# 02-MeasurementChannels.net
KiCad netlist of a schematic drawn in Altium Designer
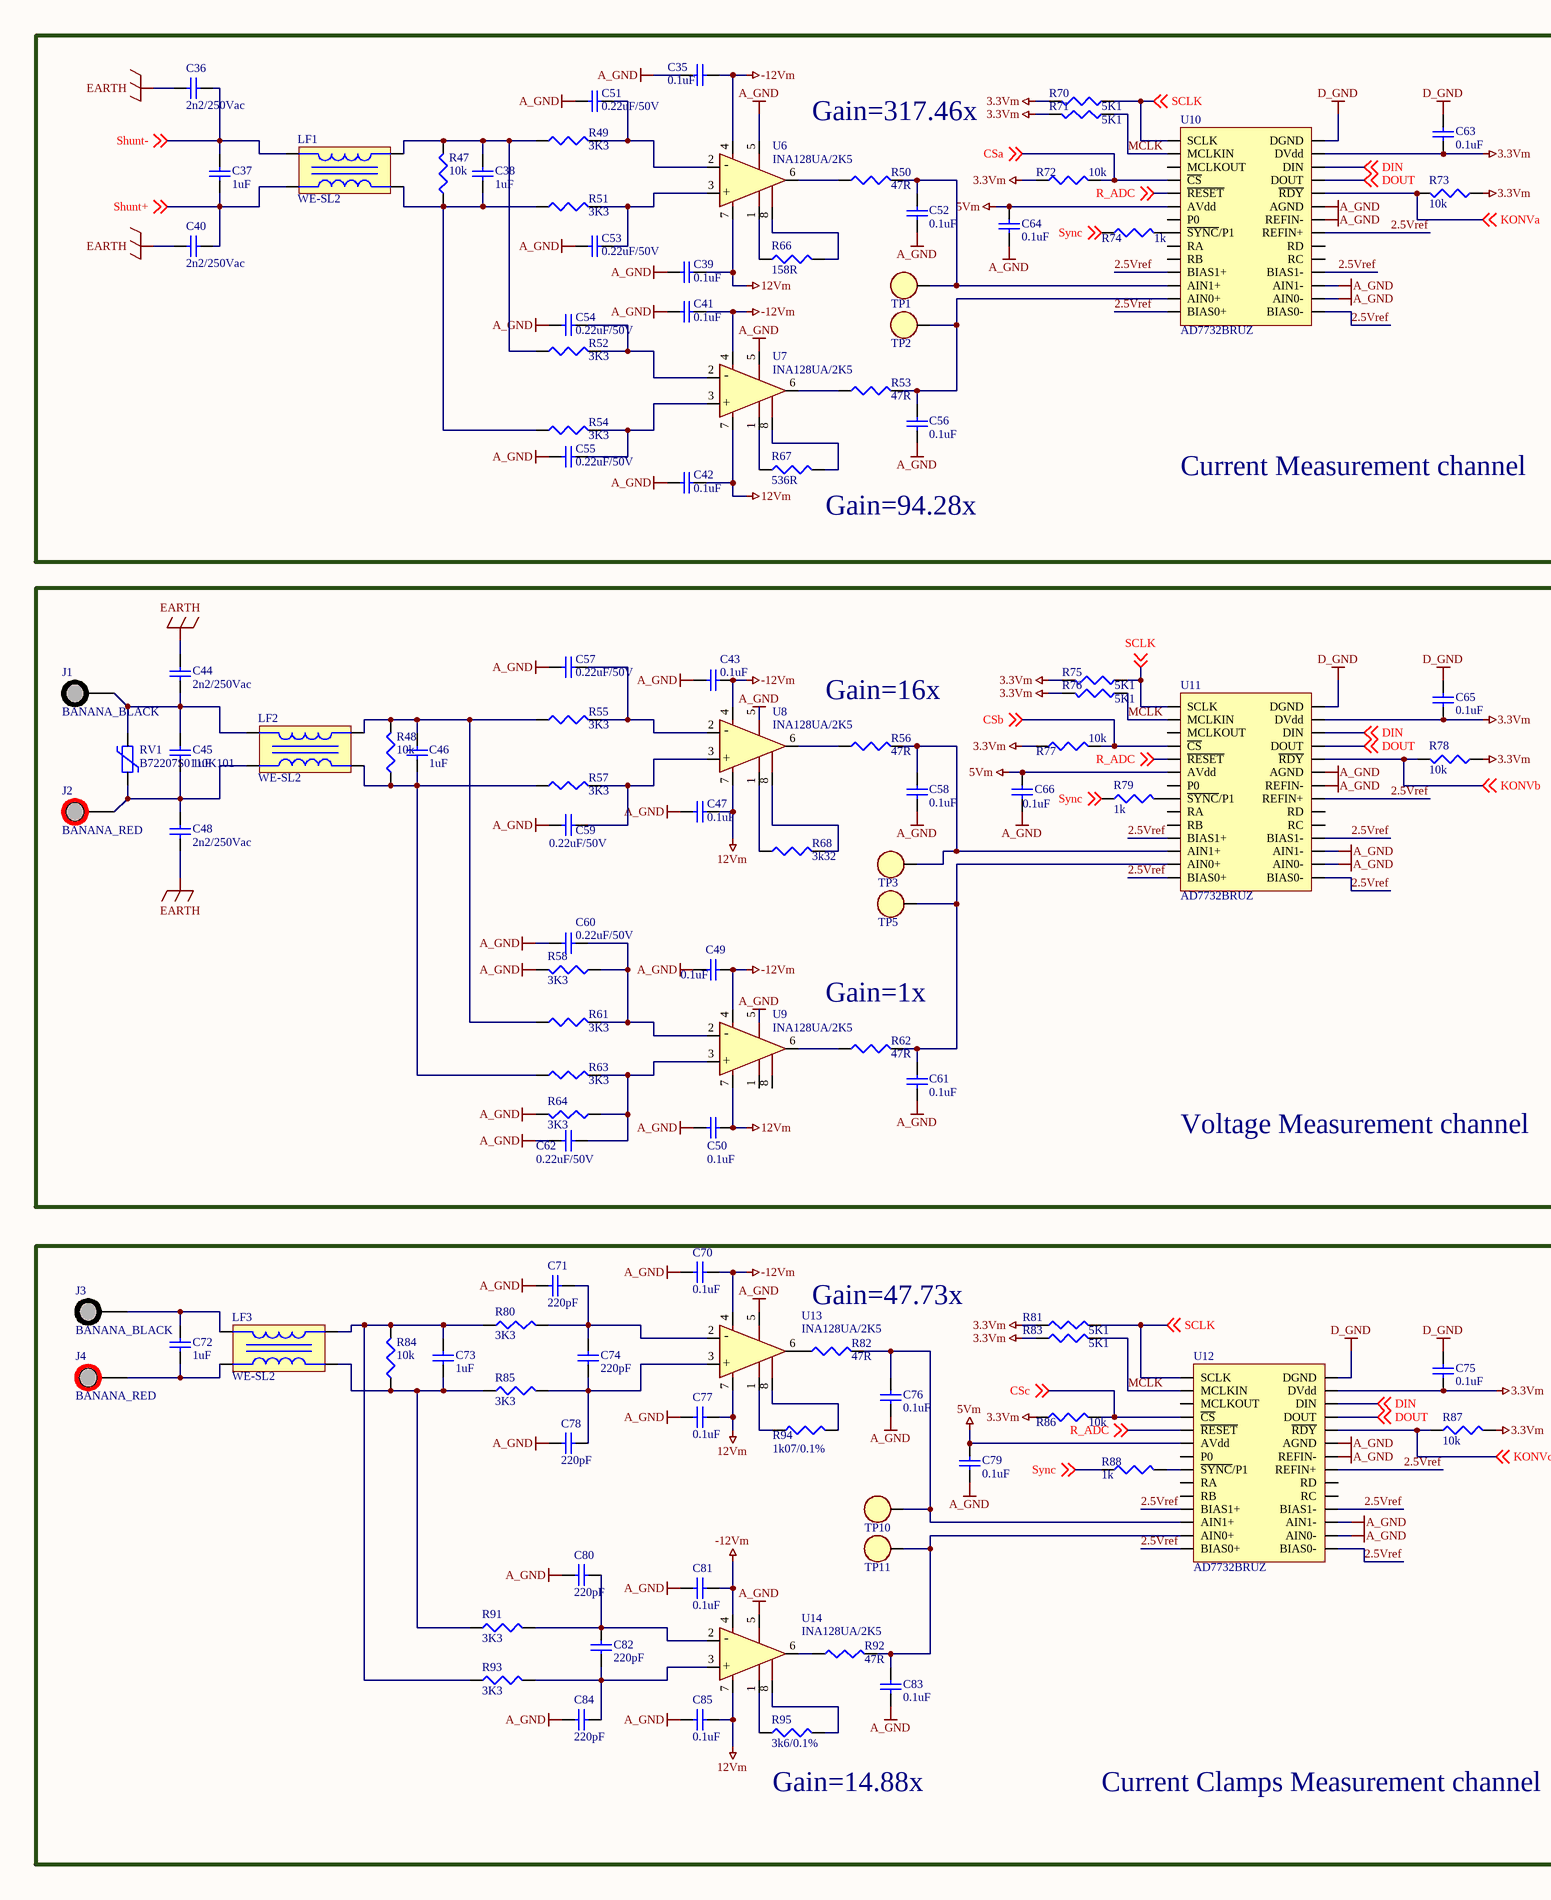
[diagram p0: 02-MeasurementChannels.SchDoc, left]
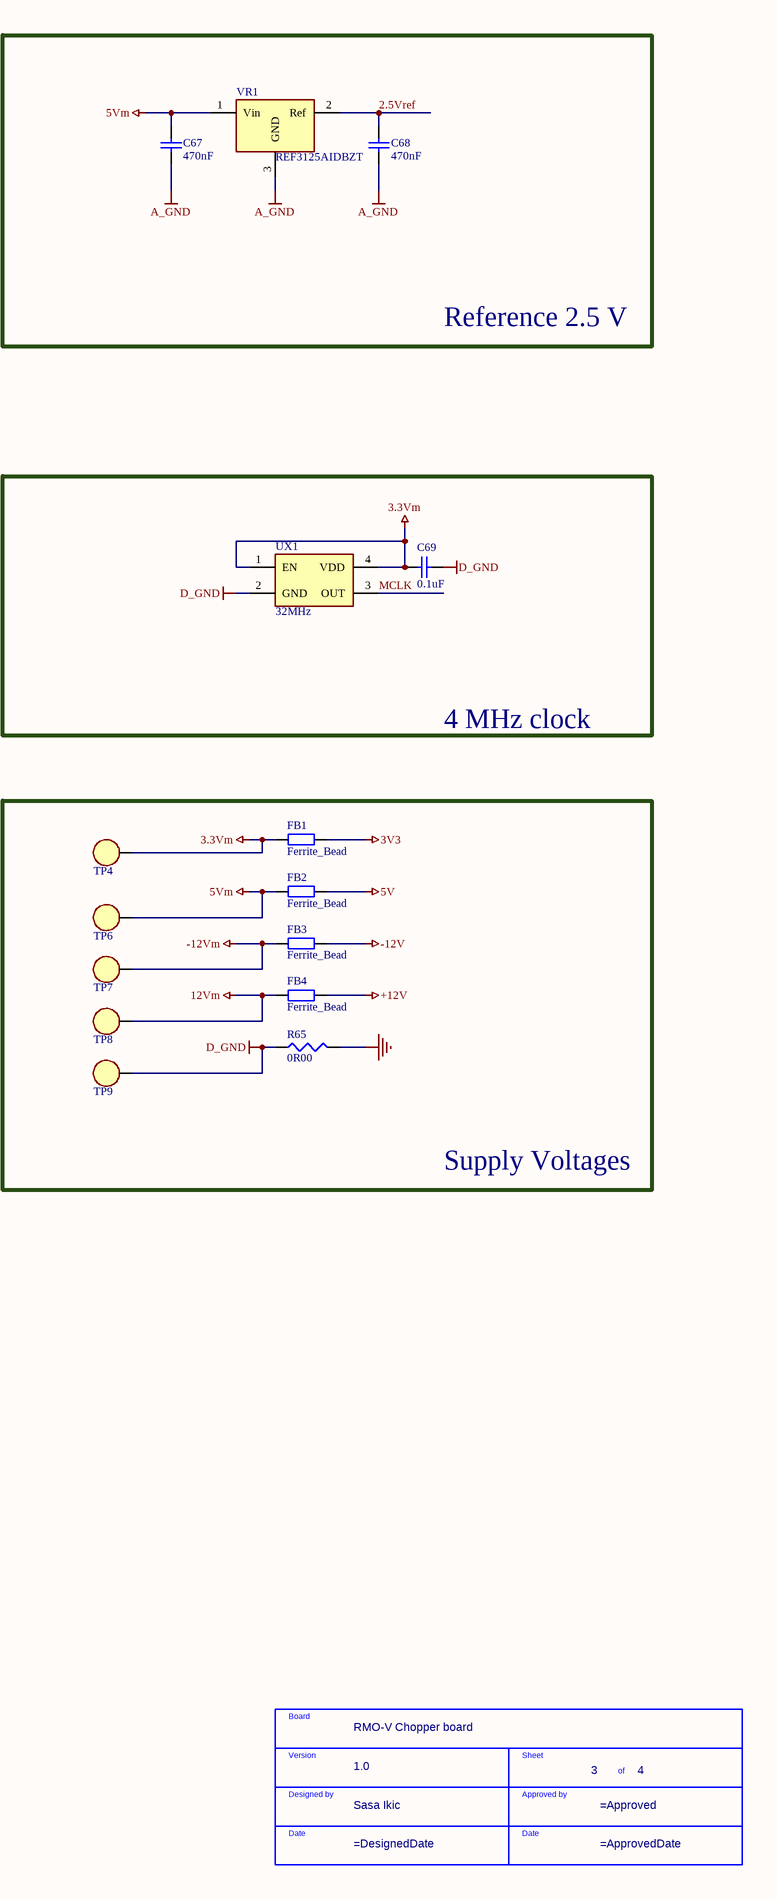
[diagram p1: 02-MeasurementChannels.SchDoc, right]

(export (version "E")
  (design (tool "Eeschema 10.0.6"))
  (components
    (comp (ref "C35")
      (value "0.1uF")
      (footprint "C0805")
      (description "CAP 0.1uF 0805 50V")
      (fields
        (field (name "MANUFACTURER") "KEMET")
        (field (name "MANUFACTURER PART NUMBER") "08055C104KAT2A")
        (field (name ".PCBCHECKED") "BP")
        (field (name ".SCHCHECKED") "BP")
      )
      (libsource (lib "My Library") (part "08055C104KAT2A"))
    )
    (comp (ref "C36")
      (value "2n2/250Vac")
      (footprint "CAPC3426X27N")
      (description "Cap Ceramic 0.0022uF 250VAC X7R 10% SMD 2220 Embossed T/R")
      (fields
        (field (name "MANUFACTURER") "Murata")
        (field (name "MANUFACTURER PART NUMBER") "GA355QR7GF222KW01L")
      )
      (libsource (lib "RMOV_chopper") (part "GA355QR7GF222KW01L"))
    )
    (comp (ref "C37")
      (value "1uF")
      (footprint "C0805")
      (description "CAP 1UF 0805 25V")
      (fields
        (field (name "MANUFACTURER") "KEMET")
        (field (name "MANUFACTURER PART NUMBER") "C0805C105K3RACTU")
        (field (name ".PCBCHECKED") "BP")
        (field (name ".SCHCHECKED") "BP")
      )
      (libsource (lib "My Library") (part "C0805C105K3RACTU"))
    )
    (comp (ref "C38")
      (value "1uF")
      (footprint "C0805")
      (description "CAP 1UF 0805 25V")
      (fields
        (field (name "MANUFACTURER") "KEMET")
        (field (name "MANUFACTURER PART NUMBER") "C0805C105K3RACTU")
        (field (name ".PCBCHECKED") "BP")
        (field (name ".SCHCHECKED") "BP")
      )
      (libsource (lib "My Library") (part "C0805C105K3RACTU"))
    )
    (comp (ref "C39")
      (value "0.1uF")
      (footprint "C0805")
      (description "CAP 0.1uF 0805 50V")
      (fields
        (field (name "MANUFACTURER") "KEMET")
        (field (name "MANUFACTURER PART NUMBER") "08055C104KAT2A")
        (field (name ".PCBCHECKED") "BP")
        (field (name ".SCHCHECKED") "BP")
      )
      (libsource (lib "My Library") (part "08055C104KAT2A"))
    )
    (comp (ref "C40")
      (value "2n2/250Vac")
      (footprint "CAPC3426X27N")
      (description "Cap Ceramic 0.0022uF 250VAC X7R 10% SMD 2220 Embossed T/R")
      (fields
        (field (name "MANUFACTURER") "Murata")
        (field (name "MANUFACTURER PART NUMBER") "GA355QR7GF222KW01L")
      )
      (libsource (lib "RMOV_chopper") (part "GA355QR7GF222KW01L"))
    )
    (comp (ref "C41")
      (value "0.1uF")
      (footprint "C0805")
      (description "CAP 0.1uF 0805 50V")
      (fields
        (field (name "MANUFACTURER") "KEMET")
        (field (name "MANUFACTURER PART NUMBER") "08055C104KAT2A")
        (field (name ".PCBCHECKED") "BP")
        (field (name ".SCHCHECKED") "BP")
      )
      (libsource (lib "My Library") (part "08055C104KAT2A"))
    )
    (comp (ref "C42")
      (value "0.1uF")
      (footprint "C0805")
      (description "CAP 0.1uF 0805 50V")
      (fields
        (field (name "MANUFACTURER") "KEMET")
        (field (name "MANUFACTURER PART NUMBER") "08055C104KAT2A")
        (field (name ".PCBCHECKED") "BP")
        (field (name ".SCHCHECKED") "BP")
      )
      (libsource (lib "My Library") (part "08055C104KAT2A"))
    )
    (comp (ref "C43")
      (value "0.1uF")
      (footprint "C0805")
      (description "CAP 0.1uF 0805 50V")
      (fields
        (field (name "MANUFACTURER") "KEMET")
        (field (name "MANUFACTURER PART NUMBER") "08055C104KAT2A")
        (field (name ".PCBCHECKED") "BP")
        (field (name ".SCHCHECKED") "BP")
      )
      (libsource (lib "My Library") (part "08055C104KAT2A"))
    )
    (comp (ref "C44")
      (value "2n2/250Vac")
      (footprint "CAPC3426X27N")
      (description "Cap Ceramic 0.0022uF 250VAC X7R 10% SMD 2220 Embossed T/R")
      (fields
        (field (name "MANUFACTURER") "Murata")
        (field (name "MANUFACTURER PART NUMBER") "GA355QR7GF222KW01L")
      )
      (libsource (lib "RMOV_chopper") (part "GA355QR7GF222KW01L"))
    )
    (comp (ref "C45")
      (value "1uF")
      (footprint "C0805")
      (description "CAP 1UF 0805 25V")
      (fields
        (field (name "MANUFACTURER") "KEMET")
        (field (name "MANUFACTURER PART NUMBER") "C0805C105K3RACTU")
        (field (name ".PCBCHECKED") "BP")
        (field (name ".SCHCHECKED") "BP")
      )
      (libsource (lib "My Library") (part "C0805C105K3RACTU"))
    )
    (comp (ref "C46")
      (value "1uF")
      (footprint "C0805")
      (description "CAP 1UF 0805 25V")
      (fields
        (field (name "MANUFACTURER") "KEMET")
        (field (name "MANUFACTURER PART NUMBER") "C0805C105K3RACTU")
        (field (name ".PCBCHECKED") "BP")
        (field (name ".SCHCHECKED") "BP")
      )
      (libsource (lib "My Library") (part "C0805C105K3RACTU"))
    )
    (comp (ref "C47")
      (value "0.1uF")
      (footprint "C0805")
      (description "CAP 0.1uF 0805 50V")
      (fields
        (field (name "MANUFACTURER") "KEMET")
        (field (name "MANUFACTURER PART NUMBER") "08055C104KAT2A")
        (field (name ".PCBCHECKED") "BP")
        (field (name ".SCHCHECKED") "BP")
      )
      (libsource (lib "My Library") (part "08055C104KAT2A"))
    )
    (comp (ref "C48")
      (value "2n2/250Vac")
      (footprint "CAPC3426X27N")
      (description "Cap Ceramic 0.0022uF 250VAC X7R 10% SMD 2220 Embossed T/R")
      (fields
        (field (name "MANUFACTURER") "Murata")
        (field (name "MANUFACTURER PART NUMBER") "GA355QR7GF222KW01L")
      )
      (libsource (lib "RMOV_chopper") (part "GA355QR7GF222KW01L"))
    )
    (comp (ref "C49")
      (value "0.1uF")
      (footprint "C0805")
      (description "CAP 0.1uF 0805 50V")
      (fields
        (field (name "MANUFACTURER") "KEMET")
        (field (name "MANUFACTURER PART NUMBER") "08055C104KAT2A")
        (field (name ".PCBCHECKED") "BP")
        (field (name ".SCHCHECKED") "BP")
      )
      (libsource (lib "My Library") (part "08055C104KAT2A"))
    )
    (comp (ref "C50")
      (value "0.1uF")
      (footprint "C0805")
      (description "CAP 0.1uF 0805 50V")
      (fields
        (field (name "MANUFACTURER") "KEMET")
        (field (name "MANUFACTURER PART NUMBER") "08055C104KAT2A")
        (field (name ".PCBCHECKED") "BP")
        (field (name ".SCHCHECKED") "BP")
      )
      (libsource (lib "My Library") (part "08055C104KAT2A"))
    )
    (comp (ref "C51")
      (value "0.22uF/50V")
      (footprint "C0805")
      (description "Cap Ceramic 0.22uF 50V X7R 10% SMD 0805 125°C Paper T/R")
      (fields
        (field (name "MANUFACTURER") "KEMET")
        (field (name "MANUFACTURER PART NUMBER") "C0805C224K5RAC7800")
      )
      (libsource (lib "RMOV_chopper") (part "C0805C224K5RAC7800"))
    )
    (comp (ref "C52")
      (value "0.1uF")
      (footprint "C0805")
      (description "CAP 0.1uF 0805 50V")
      (fields
        (field (name "MANUFACTURER") "KEMET")
        (field (name "MANUFACTURER PART NUMBER") "08055C104KAT2A")
        (field (name ".PCBCHECKED") "BP")
        (field (name ".SCHCHECKED") "BP")
      )
      (libsource (lib "My Library") (part "08055C104KAT2A"))
    )
    (comp (ref "C53")
      (value "0.22uF/50V")
      (footprint "C0805")
      (description "Cap Ceramic 0.22uF 50V X7R 10% SMD 0805 125°C Paper T/R")
      (fields
        (field (name "MANUFACTURER") "KEMET")
        (field (name "MANUFACTURER PART NUMBER") "C0805C224K5RAC7800")
      )
      (libsource (lib "RMOV_chopper") (part "C0805C224K5RAC7800"))
    )
    (comp (ref "C54")
      (value "0.22uF/50V")
      (footprint "C0805")
      (description "Cap Ceramic 0.22uF 50V X7R 10% SMD 0805 125°C Paper T/R")
      (fields
        (field (name "MANUFACTURER") "KEMET")
        (field (name "MANUFACTURER PART NUMBER") "C0805C224K5RAC7800")
      )
      (libsource (lib "RMOV_chopper") (part "C0805C224K5RAC7800"))
    )
    (comp (ref "C55")
      (value "0.22uF/50V")
      (footprint "C0805")
      (description "Cap Ceramic 0.22uF 50V X7R 10% SMD 0805 125°C Paper T/R")
      (fields
        (field (name "MANUFACTURER") "KEMET")
        (field (name "MANUFACTURER PART NUMBER") "C0805C224K5RAC7800")
      )
      (libsource (lib "RMOV_chopper") (part "C0805C224K5RAC7800"))
    )
    (comp (ref "C56")
      (value "0.1uF")
      (footprint "C0805")
      (description "CAP 0.1uF 0805 50V")
      (fields
        (field (name "MANUFACTURER") "KEMET")
        (field (name "MANUFACTURER PART NUMBER") "08055C104KAT2A")
        (field (name ".PCBCHECKED") "BP")
        (field (name ".SCHCHECKED") "BP")
      )
      (libsource (lib "My Library") (part "08055C104KAT2A"))
    )
    (comp (ref "C57")
      (value "0.22uF/50V")
      (footprint "C0805")
      (description "Cap Ceramic 0.22uF 50V X7R 10% SMD 0805 125°C Paper T/R")
      (fields
        (field (name "MANUFACTURER") "KEMET")
        (field (name "MANUFACTURER PART NUMBER") "C0805C224K5RAC7800")
      )
      (libsource (lib "RMOV_chopper") (part "C0805C224K5RAC7800"))
    )
    (comp (ref "C58")
      (value "0.1uF")
      (footprint "C0805")
      (description "CAP 0.1uF 0805 50V")
      (fields
        (field (name "MANUFACTURER") "KEMET")
        (field (name "MANUFACTURER PART NUMBER") "08055C104KAT2A")
        (field (name ".PCBCHECKED") "BP")
        (field (name ".SCHCHECKED") "BP")
      )
      (libsource (lib "My Library") (part "08055C104KAT2A"))
    )
    (comp (ref "C59")
      (value "0.22uF/50V")
      (footprint "C0805")
      (description "Cap Ceramic 0.22uF 50V X7R 10% SMD 0805 125°C Paper T/R")
      (fields
        (field (name "MANUFACTURER") "KEMET")
        (field (name "MANUFACTURER PART NUMBER") "C0805C224K5RAC7800")
      )
      (libsource (lib "RMOV_chopper") (part "C0805C224K5RAC7800"))
    )
    (comp (ref "C60")
      (value "0.22uF/50V")
      (footprint "C0805")
      (description "Cap Ceramic 0.22uF 50V X7R 10% SMD 0805 125°C Paper T/R")
      (fields
        (field (name "MANUFACTURER") "KEMET")
        (field (name "MANUFACTURER PART NUMBER") "C0805C224K5RAC7800")
      )
      (libsource (lib "RMOV_chopper") (part "C0805C224K5RAC7800"))
    )
    (comp (ref "C61")
      (value "0.1uF")
      (footprint "C0805")
      (description "CAP 0.1uF 0805 50V")
      (fields
        (field (name "MANUFACTURER") "KEMET")
        (field (name "MANUFACTURER PART NUMBER") "08055C104KAT2A")
        (field (name ".PCBCHECKED") "BP")
        (field (name ".SCHCHECKED") "BP")
      )
      (libsource (lib "My Library") (part "08055C104KAT2A"))
    )
    (comp (ref "C62")
      (value "0.22uF/50V")
      (footprint "C0805")
      (description "Cap Ceramic 0.22uF 50V X7R 10% SMD 0805 125°C Paper T/R")
      (fields
        (field (name "MANUFACTURER") "KEMET")
        (field (name "MANUFACTURER PART NUMBER") "C0805C224K5RAC7800")
      )
      (libsource (lib "RMOV_chopper") (part "C0805C224K5RAC7800"))
    )
    (comp (ref "C63")
      (value "0.1uF")
      (footprint "C0805")
      (description "CAP 0.1uF 0805 50V")
      (fields
        (field (name "MANUFACTURER") "KEMET")
        (field (name "MANUFACTURER PART NUMBER") "08055C104KAT2A")
        (field (name ".PCBCHECKED") "BP")
        (field (name ".SCHCHECKED") "BP")
      )
      (libsource (lib "My Library") (part "08055C104KAT2A"))
    )
    (comp (ref "C64")
      (value "0.1uF")
      (footprint "C0805")
      (description "CAP 0.1uF 0805 50V")
      (fields
        (field (name "MANUFACTURER") "KEMET")
        (field (name "MANUFACTURER PART NUMBER") "08055C104KAT2A")
        (field (name ".PCBCHECKED") "BP")
        (field (name ".SCHCHECKED") "BP")
      )
      (libsource (lib "My Library") (part "08055C104KAT2A"))
    )
    (comp (ref "C65")
      (value "0.1uF")
      (footprint "C0805")
      (description "CAP 0.1uF 0805 50V")
      (fields
        (field (name "MANUFACTURER") "KEMET")
        (field (name "MANUFACTURER PART NUMBER") "08055C104KAT2A")
        (field (name ".PCBCHECKED") "BP")
        (field (name ".SCHCHECKED") "BP")
      )
      (libsource (lib "My Library") (part "08055C104KAT2A"))
    )
    (comp (ref "C66")
      (value "0.1uF")
      (footprint "C0805")
      (description "CAP 0.1uF 0805 50V")
      (fields
        (field (name "MANUFACTURER") "KEMET")
        (field (name "MANUFACTURER PART NUMBER") "08055C104KAT2A")
        (field (name ".PCBCHECKED") "BP")
        (field (name ".SCHCHECKED") "BP")
      )
      (libsource (lib "My Library") (part "08055C104KAT2A"))
    )
    (comp (ref "C67")
      (value "470nF")
      (footprint "C0805")
      (description "CAP 470nF 0805 50V")
      (fields
        (field (name "MANUFACTURER") "KEMET")
        (field (name "MANUFACTURER PART NUMBER") "C0805C474K5RACTU")
      )
      (libsource (lib "My Library") (part "C0805C474K5RACTU"))
    )
    (comp (ref "C68")
      (value "470nF")
      (footprint "C0805")
      (description "CAP 470nF 0805 50V")
      (fields
        (field (name "MANUFACTURER") "KEMET")
        (field (name "MANUFACTURER PART NUMBER") "C0805C474K5RACTU")
      )
      (libsource (lib "My Library") (part "C0805C474K5RACTU"))
    )
    (comp (ref "C69")
      (value "0.1uF")
      (footprint "C0805")
      (description "CAP 0.1uF 0805 50V")
      (fields
        (field (name "MANUFACTURER") "KEMET")
        (field (name "MANUFACTURER PART NUMBER") "08055C104KAT2A")
        (field (name ".PCBCHECKED") "BP")
        (field (name ".SCHCHECKED") "BP")
      )
      (libsource (lib "My Library") (part "08055C104KAT2A"))
    )
    (comp (ref "C70")
      (value "0.1uF")
      (footprint "C0805")
      (description "CAP 0.1uF 0805 50V")
      (fields
        (field (name "MANUFACTURER") "KEMET")
        (field (name "MANUFACTURER PART NUMBER") "08055C104KAT2A")
        (field (name ".PCBCHECKED") "BP")
        (field (name ".SCHCHECKED") "BP")
      )
      (libsource (lib "My Library") (part "08055C104KAT2A"))
    )
    (comp (ref "C71")
      (value "220pF")
      (footprint "C0805")
      (description "CAP 220PF 0805 50V")
      (fields
        (field (name "MANUFACTURER") "KEMET")
        (field (name "MANUFACTURER PART NUMBER") "C0805C221J5GAC-TU")
      )
      (libsource (lib "My Library") (part "C0805C221J5GAC-TU"))
    )
    (comp (ref "C72")
      (value "1uF")
      (footprint "C0805")
      (description "CAP 1UF 0805 25V")
      (fields
        (field (name "MANUFACTURER") "KEMET")
        (field (name "MANUFACTURER PART NUMBER") "C0805C105K3RACTU")
        (field (name ".PCBCHECKED") "BP")
        (field (name ".SCHCHECKED") "BP")
      )
      (libsource (lib "My Library") (part "C0805C105K3RACTU"))
    )
    (comp (ref "C73")
      (value "1uF")
      (footprint "C0805")
      (description "CAP 1UF 0805 25V")
      (fields
        (field (name "MANUFACTURER") "KEMET")
        (field (name "MANUFACTURER PART NUMBER") "C0805C105K3RACTU")
        (field (name ".PCBCHECKED") "BP")
        (field (name ".SCHCHECKED") "BP")
      )
      (libsource (lib "My Library") (part "C0805C105K3RACTU"))
    )
    (comp (ref "C74")
      (value "220pF")
      (footprint "C0805")
      (description "CAP 220PF 0805 50V")
      (fields
        (field (name "MANUFACTURER") "KEMET")
        (field (name "MANUFACTURER PART NUMBER") "C0805C221J5GAC-TU")
      )
      (libsource (lib "My Library") (part "C0805C221J5GAC-TU"))
    )
    (comp (ref "C75")
      (value "0.1uF")
      (footprint "C0805")
      (description "CAP 0.1uF 0805 50V")
      (fields
        (field (name "MANUFACTURER") "KEMET")
        (field (name "MANUFACTURER PART NUMBER") "08055C104KAT2A")
        (field (name ".PCBCHECKED") "BP")
        (field (name ".SCHCHECKED") "BP")
      )
      (libsource (lib "My Library") (part "08055C104KAT2A"))
    )
    (comp (ref "C76")
      (value "0.1uF")
      (footprint "C0805")
      (description "CAP 0.1uF 0805 50V")
      (fields
        (field (name "MANUFACTURER") "KEMET")
        (field (name "MANUFACTURER PART NUMBER") "08055C104KAT2A")
        (field (name ".PCBCHECKED") "BP")
        (field (name ".SCHCHECKED") "BP")
      )
      (libsource (lib "My Library") (part "08055C104KAT2A"))
    )
    (comp (ref "C77")
      (value "0.1uF")
      (footprint "C0805")
      (description "CAP 0.1uF 0805 50V")
      (fields
        (field (name "MANUFACTURER") "KEMET")
        (field (name "MANUFACTURER PART NUMBER") "08055C104KAT2A")
        (field (name ".PCBCHECKED") "BP")
        (field (name ".SCHCHECKED") "BP")
      )
      (libsource (lib "My Library") (part "08055C104KAT2A"))
    )
    (comp (ref "C78")
      (value "220pF")
      (footprint "C0805")
      (description "CAP 220PF 0805 50V")
      (fields
        (field (name "MANUFACTURER") "KEMET")
        (field (name "MANUFACTURER PART NUMBER") "C0805C221J5GAC-TU")
      )
      (libsource (lib "My Library") (part "C0805C221J5GAC-TU"))
    )
    (comp (ref "C79")
      (value "0.1uF")
      (footprint "C0805")
      (description "CAP 0.1uF 0805 50V")
      (fields
        (field (name "MANUFACTURER") "KEMET")
        (field (name "MANUFACTURER PART NUMBER") "08055C104KAT2A")
        (field (name ".PCBCHECKED") "BP")
        (field (name ".SCHCHECKED") "BP")
      )
      (libsource (lib "My Library") (part "08055C104KAT2A"))
    )
    (comp (ref "C80")
      (value "220pF")
      (footprint "C0805")
      (description "CAP 220PF 0805 50V")
      (fields
        (field (name "MANUFACTURER") "KEMET")
        (field (name "MANUFACTURER PART NUMBER") "C0805C221J5GAC-TU")
      )
      (libsource (lib "My Library") (part "C0805C221J5GAC-TU"))
    )
    (comp (ref "C81")
      (value "0.1uF")
      (footprint "C0805")
      (description "CAP 0.1uF 0805 50V")
      (fields
        (field (name "MANUFACTURER") "KEMET")
        (field (name "MANUFACTURER PART NUMBER") "08055C104KAT2A")
        (field (name ".PCBCHECKED") "BP")
        (field (name ".SCHCHECKED") "BP")
      )
      (libsource (lib "My Library") (part "08055C104KAT2A"))
    )
    (comp (ref "C82")
      (value "220pF")
      (footprint "C0805")
      (description "CAP 220PF 0805 50V")
      (fields
        (field (name "MANUFACTURER") "KEMET")
        (field (name "MANUFACTURER PART NUMBER") "C0805C221J5GAC-TU")
      )
      (libsource (lib "My Library") (part "C0805C221J5GAC-TU"))
    )
    (comp (ref "C83")
      (value "0.1uF")
      (footprint "C0805")
      (description "CAP 0.1uF 0805 50V")
      (fields
        (field (name "MANUFACTURER") "KEMET")
        (field (name "MANUFACTURER PART NUMBER") "08055C104KAT2A")
        (field (name ".PCBCHECKED") "BP")
        (field (name ".SCHCHECKED") "BP")
      )
      (libsource (lib "My Library") (part "08055C104KAT2A"))
    )
    (comp (ref "C84")
      (value "220pF")
      (footprint "C0805")
      (description "CAP 220PF 0805 50V")
      (fields
        (field (name "MANUFACTURER") "KEMET")
        (field (name "MANUFACTURER PART NUMBER") "C0805C221J5GAC-TU")
      )
      (libsource (lib "My Library") (part "C0805C221J5GAC-TU"))
    )
    (comp (ref "C85")
      (value "0.1uF")
      (footprint "C0805")
      (description "CAP 0.1uF 0805 50V")
      (fields
        (field (name "MANUFACTURER") "KEMET")
        (field (name "MANUFACTURER PART NUMBER") "08055C104KAT2A")
        (field (name ".PCBCHECKED") "BP")
        (field (name ".SCHCHECKED") "BP")
      )
      (libsource (lib "My Library") (part "08055C104KAT2A"))
    )
    (comp (ref "FB1")
      (value "Ferrite_Bead")
      (footprint "FB0805")
      (description "FERRITE 300mA 0805 0.35R")
      (fields
        (field (name "MANUFACTURER") "FAIR-RITE")
        (field (name "MANUFACTURER PART NUMBER") "2508056017Y0")
        (field (name ".PCBCHECKED") "BP")
        (field (name ".SCHCHECKED") "BP")
      )
      (libsource (lib "My Library") (part "2508056017Y0"))
    )
    (comp (ref "FB2")
      (value "Ferrite_Bead")
      (footprint "FB0805")
      (description "FERRITE 300mA 0805 0.35R")
      (fields
        (field (name "MANUFACTURER") "FAIR-RITE")
        (field (name "MANUFACTURER PART NUMBER") "2508056017Y0")
        (field (name ".PCBCHECKED") "BP")
        (field (name ".SCHCHECKED") "BP")
      )
      (libsource (lib "My Library") (part "2508056017Y0"))
    )
    (comp (ref "FB3")
      (value "Ferrite_Bead")
      (footprint "FB0805")
      (description "FERRITE 300mA 0805 0.35R")
      (fields
        (field (name "MANUFACTURER") "FAIR-RITE")
        (field (name "MANUFACTURER PART NUMBER") "2508056017Y0")
        (field (name ".PCBCHECKED") "BP")
        (field (name ".SCHCHECKED") "BP")
      )
      (libsource (lib "My Library") (part "2508056017Y0"))
    )
    (comp (ref "FB4")
      (value "Ferrite_Bead")
      (footprint "FB0805")
      (description "FERRITE 300mA 0805 0.35R")
      (fields
        (field (name "MANUFACTURER") "FAIR-RITE")
        (field (name "MANUFACTURER PART NUMBER") "2508056017Y0")
        (field (name ".PCBCHECKED") "BP")
        (field (name ".SCHCHECKED") "BP")
      )
      (libsource (lib "My Library") (part "2508056017Y0"))
    )
    (comp (ref "J1")
      (value "BANANA_BLACK")
      (footprint "BANANA_THT_BLACK")
      (description "BANANA SOCKET PCB 4MM R/A BLACK")
      (fields
        (field (name "MANUFACTURER") "Multi-Contact")
        (field (name "MANUFACTURER PART NUMBER") "66.9040-21")
      )
      (libsource (lib "My Library") (part "66.9040-21"))
    )
    (comp (ref "J2")
      (value "BANANA_RED")
      (footprint "BANANA_THT_RED")
      (description "BANANA 66.9040-22 SOCKET PCB 4MM R/A RED")
      (fields
        (field (name "MANUFACTURER") "Multi-Contact")
        (field (name "MANUFACTURER PART NUMBER") "66.9040-22")
      )
      (libsource (lib "My Library") (part "66.9040-22"))
    )
    (comp (ref "J3")
      (value "BANANA_BLACK")
      (footprint "BANANA_THT_BLACK")
      (description "BANANA SOCKET PCB 4MM R/A BLACK")
      (fields
        (field (name "MANUFACTURER") "Multi-Contact")
        (field (name "MANUFACTURER PART NUMBER") "66.9040-21")
      )
      (libsource (lib "My Library") (part "66.9040-21"))
    )
    (comp (ref "J4")
      (value "BANANA_RED")
      (footprint "BANANA_THT_RED")
      (description "BANANA 66.9040-22 SOCKET PCB 4MM R/A RED")
      (fields
        (field (name "MANUFACTURER") "Multi-Contact")
        (field (name "MANUFACTURER PART NUMBER") "66.9040-22")
      )
      (libsource (lib "My Library") (part "66.9040-22"))
    )
    (comp (ref "LF1")
      (value "WE-SL2")
      (footprint "SOJ254P940X500-4M")
      (description "6.5mH @ 10kHz 2 Line Common Mode Choke Surface Mount 18.4 kOhms @ 700kHz 400mA DCR 950mOhm")
      (fields
        (field (name "MANUFACTURER") "Würth Elektronik")
        (field (name "MANUFACTURER PART NUMBER") "744229")
      )
      (libsource (lib "RMOV_chopper") (part "WE-SL2"))
    )
    (comp (ref "LF2")
      (value "WE-SL2")
      (footprint "SOJ254P940X500-4M")
      (description "6.5mH @ 10kHz 2 Line Common Mode Choke Surface Mount 18.4 kOhms @ 700kHz 400mA DCR 950mOhm")
      (fields
        (field (name "MANUFACTURER") "Würth Elektronik")
        (field (name "MANUFACTURER PART NUMBER") "744229")
      )
      (libsource (lib "RMOV_chopper") (part "WE-SL2"))
    )
    (comp (ref "LF3")
      (value "WE-SL2")
      (footprint "SOJ254P940X500-4M")
      (description "6.5mH @ 10kHz 2 Line Common Mode Choke Surface Mount 18.4 kOhms @ 700kHz 400mA DCR 950mOhm")
      (fields
        (field (name "MANUFACTURER") "Würth Elektronik")
        (field (name "MANUFACTURER PART NUMBER") "744229")
      )
      (libsource (lib "RMOV_chopper") (part "WE-SL2"))
    )
    (comp (ref "R47")
      (value "10k")
      (footprint "R0805")
      (description "RES 10K 0805 0.125W 1%")
      (fields
        (field (name "MANUFACTURER") "Vishay Dale")
        (field (name "MANUFACTURER PART NUMBER") "CRCW080510K0FKEA")
        (field (name ".PCBCHECKED") "BP")
        (field (name ".SCHCHECKED") "BP")
      )
      (libsource (lib "My Library") (part "CRCW080510K0FKEA"))
    )
    (comp (ref "R48")
      (value "10k")
      (footprint "R0805")
      (description "RES 10K 0805 0.125W 1%")
      (fields
        (field (name "MANUFACTURER") "Vishay Dale")
        (field (name "MANUFACTURER PART NUMBER") "CRCW080510K0FKEA")
        (field (name ".PCBCHECKED") "BP")
        (field (name ".SCHCHECKED") "BP")
      )
      (libsource (lib "My Library") (part "CRCW080510K0FKEA"))
    )
    (comp (ref "R49")
      (value "3K3")
      (footprint "R0805")
      (description "RES 3K3 SMD 0805")
      (fields
        (field (name "MANUFACTURER") "Yageo")
        (field (name "MANUFACTURER PART NUMBER") "RC0805FR-073K3L")
      )
      (libsource (lib "My Library") (part "RC0805FR-073K3L"))
    )
    (comp (ref "R50")
      (value "47R")
      (footprint "R0805")
      (description "RC Series 0805 0.125 W 47 Ohm ±1% ±100 ppm/°C SMT Thick Film Chip Resistor")
      (fields
        (field (name "MANUFACTURER") "Yageo")
        (field (name "MANUFACTURER PART NUMBER") "RC0805FR-0747RL")
      )
      (libsource (lib "RMOV_chopper") (part "RC0805FR-0747RL"))
    )
    (comp (ref "R51")
      (value "3K3")
      (footprint "R0805")
      (description "RES 3K3 SMD 0805")
      (fields
        (field (name "MANUFACTURER") "Yageo")
        (field (name "MANUFACTURER PART NUMBER") "RC0805FR-073K3L")
      )
      (libsource (lib "My Library") (part "RC0805FR-073K3L"))
    )
    (comp (ref "R52")
      (value "3K3")
      (footprint "R0805")
      (description "RES 3K3 SMD 0805")
      (fields
        (field (name "MANUFACTURER") "Yageo")
        (field (name "MANUFACTURER PART NUMBER") "RC0805FR-073K3L")
      )
      (libsource (lib "My Library") (part "RC0805FR-073K3L"))
    )
    (comp (ref "R53")
      (value "47R")
      (footprint "R0805")
      (description "RC Series 0805 0.125 W 47 Ohm ±1% ±100 ppm/°C SMT Thick Film Chip Resistor")
      (fields
        (field (name "MANUFACTURER") "Yageo")
        (field (name "MANUFACTURER PART NUMBER") "RC0805FR-0747RL")
      )
      (libsource (lib "RMOV_chopper") (part "RC0805FR-0747RL"))
    )
    (comp (ref "R54")
      (value "3K3")
      (footprint "R0805")
      (description "RES 3K3 SMD 0805")
      (fields
        (field (name "MANUFACTURER") "Yageo")
        (field (name "MANUFACTURER PART NUMBER") "RC0805FR-073K3L")
      )
      (libsource (lib "My Library") (part "RC0805FR-073K3L"))
    )
    (comp (ref "R55")
      (value "3K3")
      (footprint "R0805")
      (description "RES 3K3 SMD 0805")
      (fields
        (field (name "MANUFACTURER") "Yageo")
        (field (name "MANUFACTURER PART NUMBER") "RC0805FR-073K3L")
      )
      (libsource (lib "My Library") (part "RC0805FR-073K3L"))
    )
    (comp (ref "R56")
      (value "47R")
      (footprint "R0805")
      (description "RC Series 0805 0.125 W 47 Ohm ±1% ±100 ppm/°C SMT Thick Film Chip Resistor")
      (fields
        (field (name "MANUFACTURER") "Yageo")
        (field (name "MANUFACTURER PART NUMBER") "RC0805FR-0747RL")
      )
      (libsource (lib "RMOV_chopper") (part "RC0805FR-0747RL"))
    )
    (comp (ref "R57")
      (value "3K3")
      (footprint "R0805")
      (description "RES 3K3 SMD 0805")
      (fields
        (field (name "MANUFACTURER") "Yageo")
        (field (name "MANUFACTURER PART NUMBER") "RC0805FR-073K3L")
      )
      (libsource (lib "My Library") (part "RC0805FR-073K3L"))
    )
    (comp (ref "R58")
      (value "3K3")
      (footprint "R0805")
      (description "RES 3K3 SMD 0805")
      (fields
        (field (name "MANUFACTURER") "Yageo")
        (field (name "MANUFACTURER PART NUMBER") "RC0805FR-073K3L")
      )
      (libsource (lib "My Library") (part "RC0805FR-073K3L"))
    )
    (comp (ref "R61")
      (value "3K3")
      (footprint "R0805")
      (description "RES 3K3 SMD 0805")
      (fields
        (field (name "MANUFACTURER") "Yageo")
        (field (name "MANUFACTURER PART NUMBER") "RC0805FR-073K3L")
      )
      (libsource (lib "My Library") (part "RC0805FR-073K3L"))
    )
    (comp (ref "R62")
      (value "47R")
      (footprint "R0805")
      (description "RC Series 0805 0.125 W 47 Ohm ±1% ±100 ppm/°C SMT Thick Film Chip Resistor")
      (fields
        (field (name "MANUFACTURER") "Yageo")
        (field (name "MANUFACTURER PART NUMBER") "RC0805FR-0747RL")
      )
      (libsource (lib "RMOV_chopper") (part "RC0805FR-0747RL"))
    )
    (comp (ref "R63")
      (value "3K3")
      (footprint "R0805")
      (description "RES 3K3 SMD 0805")
      (fields
        (field (name "MANUFACTURER") "Yageo")
        (field (name "MANUFACTURER PART NUMBER") "RC0805FR-073K3L")
      )
      (libsource (lib "My Library") (part "RC0805FR-073K3L"))
    )
    (comp (ref "R64")
      (value "3K3")
      (footprint "R0805")
      (description "RES 3K3 SMD 0805")
      (fields
        (field (name "MANUFACTURER") "Yageo")
        (field (name "MANUFACTURER PART NUMBER") "RC0805FR-073K3L")
      )
      (libsource (lib "My Library") (part "RC0805FR-073K3L"))
    )
    (comp (ref "R65")
      (value "0R00")
      (footprint "R0805")
      (description "Res Thick Film 0805 0 Ohm Jumper Molded SMD Paper T/R")
      (fields
        (field (name "MANUFACTURER") "Yageo")
        (field (name "MANUFACTURER PART NUMBER") "RC0805FR-070RL")
      )
      (libsource (lib "RMOV_chopper") (part "RC0805FR-070RL"))
    )
    (comp (ref "R66")
      (value "158R")
      (footprint "R0805")
      (fields
        (field (name "MANUFACTURER") "TE CONNECTIVITY")
        (field (name "MANUFACTURER PART NUMBER") "RP73D2A158RBTG")
        (field (name "TOLERANCE") "0.1%")
      )
      (libsource (lib "RMOV_chopper") (part "RP73D2A158RBTG"))
    )
    (comp (ref "R67")
      (value "536R")
      (footprint "R0805")
      (fields
        (field (name "MANUFACTURER") "TE CONNECTIVITY")
        (field (name "MANUFACTURER PART NUMBER") "RN73C2A536RBTDF")
        (field (name "TOLERANCE") "0.1%")
      )
      (libsource (lib "RMOV_chopper") (part "RN73C2A536RBTDF"))
    )
    (comp (ref "R68")
      (value "3k32")
      (footprint "R0805")
      (description "ERA6AEB3321V - SMD Resistor, Metal Thin Film 3.32 kOhm, ± 0.1 %, Panasonic")
      (fields
        (field (name "MANUFACTURER") "Panasonic")
        (field (name "MANUFACTURER PART NUMBER") "ERA6AEB3321V")
      )
      (libsource (lib "RMOV_chopper") (part "ERA6AEB3321V"))
    )
    (comp (ref "R70")
      (value "5K1")
      (footprint "R0805")
      (description "RES 5K1 0805 0.125W 1%")
      (fields
        (field (name "MANUFACTURER") "Vishay")
        (field (name "MANUFACTURER PART NUMBER") "CRCW08055K10FKEA")
      )
      (libsource (lib "My Library") (part "CRCW08055K10FKEA"))
    )
    (comp (ref "R71")
      (value "5K1")
      (footprint "R0805")
      (description "RES 5K1 0805 0.125W 1%")
      (fields
        (field (name "MANUFACTURER") "Vishay")
        (field (name "MANUFACTURER PART NUMBER") "CRCW08055K10FKEA")
      )
      (libsource (lib "My Library") (part "CRCW08055K10FKEA"))
    )
    (comp (ref "R72")
      (value "10k")
      (footprint "R0805")
      (description "RES 10K 0805 0.125W 1%")
      (fields
        (field (name "MANUFACTURER") "Vishay Dale")
        (field (name "MANUFACTURER PART NUMBER") "CRCW080510K0FKEA")
        (field (name ".PCBCHECKED") "BP")
        (field (name ".SCHCHECKED") "BP")
      )
      (libsource (lib "My Library") (part "CRCW080510K0FKEA"))
    )
    (comp (ref "R73")
      (value "10k")
      (footprint "R0805")
      (description "RES 10K 0805 0.125W 1%")
      (fields
        (field (name "MANUFACTURER") "Vishay Dale")
        (field (name "MANUFACTURER PART NUMBER") "CRCW080510K0FKEA")
        (field (name ".PCBCHECKED") "BP")
        (field (name ".SCHCHECKED") "BP")
      )
      (libsource (lib "My Library") (part "CRCW080510K0FKEA"))
    )
    (comp (ref "R74")
      (value "1k")
      (footprint "R0805")
      (description "RES 1K 0805 0.125W 1%")
      (fields
        (field (name "MANUFACTURER") "Vishay Dale")
        (field (name "MANUFACTURER PART NUMBER") "CRCW08051K00FKEA")
        (field (name ".PCBCHECKED") "BP")
        (field (name ".SCHCHECKED") "BP")
      )
      (libsource (lib "My Library") (part "CRCW08051K00FKEA"))
    )
    (comp (ref "R75")
      (value "5K1")
      (footprint "R0805")
      (description "RES 5K1 0805 0.125W 1%")
      (fields
        (field (name "MANUFACTURER") "Vishay")
        (field (name "MANUFACTURER PART NUMBER") "CRCW08055K10FKEA")
      )
      (libsource (lib "My Library") (part "CRCW08055K10FKEA"))
    )
    (comp (ref "R76")
      (value "5K1")
      (footprint "R0805")
      (description "RES 5K1 0805 0.125W 1%")
      (fields
        (field (name "MANUFACTURER") "Vishay")
        (field (name "MANUFACTURER PART NUMBER") "CRCW08055K10FKEA")
      )
      (libsource (lib "My Library") (part "CRCW08055K10FKEA"))
    )
    (comp (ref "R77")
      (value "10k")
      (footprint "R0805")
      (description "RES 10K 0805 0.125W 1%")
      (fields
        (field (name "MANUFACTURER") "Vishay Dale")
        (field (name "MANUFACTURER PART NUMBER") "CRCW080510K0FKEA")
        (field (name ".PCBCHECKED") "BP")
        (field (name ".SCHCHECKED") "BP")
      )
      (libsource (lib "My Library") (part "CRCW080510K0FKEA"))
    )
    (comp (ref "R78")
      (value "10k")
      (footprint "R0805")
      (description "RES 10K 0805 0.125W 1%")
      (fields
        (field (name "MANUFACTURER") "Vishay Dale")
        (field (name "MANUFACTURER PART NUMBER") "CRCW080510K0FKEA")
        (field (name ".PCBCHECKED") "BP")
        (field (name ".SCHCHECKED") "BP")
      )
      (libsource (lib "My Library") (part "CRCW080510K0FKEA"))
    )
    (comp (ref "R79")
      (value "1k")
      (footprint "R0805")
      (description "RES 1K 0805 0.125W 1%")
      (fields
        (field (name "MANUFACTURER") "Vishay Dale")
        (field (name "MANUFACTURER PART NUMBER") "CRCW08051K00FKEA")
        (field (name ".PCBCHECKED") "BP")
        (field (name ".SCHCHECKED") "BP")
      )
      (libsource (lib "My Library") (part "CRCW08051K00FKEA"))
    )
    (comp (ref "R80")
      (value "3K3")
      (footprint "R0805")
      (description "RES 3K3 SMD 0805")
      (fields
        (field (name "MANUFACTURER") "Yageo")
        (field (name "MANUFACTURER PART NUMBER") "RC0805FR-073K3L")
      )
      (libsource (lib "My Library") (part "RC0805FR-073K3L"))
    )
    (comp (ref "R81")
      (value "5K1")
      (footprint "R0805")
      (description "RES 5K1 0805 0.125W 1%")
      (fields
        (field (name "MANUFACTURER") "Vishay")
        (field (name "MANUFACTURER PART NUMBER") "CRCW08055K10FKEA")
      )
      (libsource (lib "My Library") (part "CRCW08055K10FKEA"))
    )
    (comp (ref "R82")
      (value "47R")
      (footprint "R0805")
      (description "RES 47R 0805 0.125W 1%")
      (fields
        (field (name "MANUFACTURER") "Vishay")
        (field (name "MANUFACTURER PART NUMBER") "CRCW080547R0FKEA")
      )
      (libsource (lib "My Library") (part "CRCW080547R0FKEA"))
    )
    (comp (ref "R83")
      (value "5K1")
      (footprint "R0805")
      (description "RES 5K1 0805 0.125W 1%")
      (fields
        (field (name "MANUFACTURER") "Vishay")
        (field (name "MANUFACTURER PART NUMBER") "CRCW08055K10FKEA")
      )
      (libsource (lib "My Library") (part "CRCW08055K10FKEA"))
    )
    (comp (ref "R84")
      (value "10k")
      (footprint "R0805")
      (description "RES 10K 0805 0.125W 1%")
      (fields
        (field (name "MANUFACTURER") "Vishay Dale")
        (field (name "MANUFACTURER PART NUMBER") "CRCW080510K0FKEA")
        (field (name ".PCBCHECKED") "BP")
        (field (name ".SCHCHECKED") "BP")
      )
      (libsource (lib "My Library") (part "CRCW080510K0FKEA"))
    )
    (comp (ref "R85")
      (value "3K3")
      (footprint "R0805")
      (description "RES 3K3 SMD 0805")
      (fields
        (field (name "MANUFACTURER") "Yageo")
        (field (name "MANUFACTURER PART NUMBER") "RC0805FR-073K3L")
      )
      (libsource (lib "My Library") (part "RC0805FR-073K3L"))
    )
    (comp (ref "R86")
      (value "10k")
      (footprint "R0805")
      (description "RES 10K 0805 0.125W 1%")
      (fields
        (field (name "MANUFACTURER") "Vishay Dale")
        (field (name "MANUFACTURER PART NUMBER") "CRCW080510K0FKEA")
        (field (name ".PCBCHECKED") "BP")
        (field (name ".SCHCHECKED") "BP")
      )
      (libsource (lib "My Library") (part "CRCW080510K0FKEA"))
    )
    (comp (ref "R87")
      (value "10k")
      (footprint "R0805")
      (description "RES 10K 0805 0.125W 1%")
      (fields
        (field (name "MANUFACTURER") "Vishay Dale")
        (field (name "MANUFACTURER PART NUMBER") "CRCW080510K0FKEA")
        (field (name ".PCBCHECKED") "BP")
        (field (name ".SCHCHECKED") "BP")
      )
      (libsource (lib "My Library") (part "CRCW080510K0FKEA"))
    )
    (comp (ref "R88")
      (value "1k")
      (footprint "R0805")
      (description "RES 1K 0805 0.125W 1%")
      (fields
        (field (name "MANUFACTURER") "Vishay Dale")
        (field (name "MANUFACTURER PART NUMBER") "CRCW08051K00FKEA")
        (field (name ".PCBCHECKED") "BP")
        (field (name ".SCHCHECKED") "BP")
      )
      (libsource (lib "My Library") (part "CRCW08051K00FKEA"))
    )
    (comp (ref "R91")
      (value "3K3")
      (footprint "R0805")
      (description "RES 3K3 SMD 0805")
      (fields
        (field (name "MANUFACTURER") "Yageo")
        (field (name "MANUFACTURER PART NUMBER") "RC0805FR-073K3L")
      )
      (libsource (lib "My Library") (part "RC0805FR-073K3L"))
    )
    (comp (ref "R92")
      (value "47R")
      (footprint "R0805")
      (description "RES 47R 0805 0.125W 1%")
      (fields
        (field (name "MANUFACTURER") "Vishay")
        (field (name "MANUFACTURER PART NUMBER") "CRCW080547R0FKEA")
      )
      (libsource (lib "My Library") (part "CRCW080547R0FKEA"))
    )
    (comp (ref "R93")
      (value "3K3")
      (footprint "R0805")
      (description "RES 3K3 SMD 0805")
      (fields
        (field (name "MANUFACTURER") "Yageo")
        (field (name "MANUFACTURER PART NUMBER") "RC0805FR-073K3L")
      )
      (libsource (lib "My Library") (part "RC0805FR-073K3L"))
    )
    (comp (ref "R94")
      (value "1k07/0.1%")
      (footprint "R0805")
      (fields
        (field (name "MANUFACTURER") "Panasonic")
        (field (name "MANUFACTURER PART NUMBER") "ERA6AEB1071V")
        (field (name "TOLERANCE") "0.1%")
      )
      (libsource (lib "RMOV_chopper") (part "ERA6AEB1071V"))
    )
    (comp (ref "R95")
      (value "3k6/0.1%")
      (footprint "R0805")
      (description "ERA6AEB362V - SMD Resistor, Metal Thin Film 3.6 kOhm, ± 0.1 %, Panasonic")
      (fields
        (field (name "MANUFACTURER") "Panasonic")
        (field (name "MANUFACTURER PART NUMBER") "ERA6AEB362V")
      )
      (libsource (lib "RMO-V_LibSch") (part "ERA6AEB362V"))
    )
    (comp (ref "RV1")
      (value "B72207S0110K101")
      (footprint "S20K300")
      (description "VARISTOR 11VAC S20K300 250A")
      (fields (field (name "MANUFACTURER") "TDK EPCOS"))
      (libsource (lib "My Library") (part "B72207S0110K101"))
    )
    (comp (ref "TP1")
      (value "-")
      (footprint "TESTPOINT_0.8X1.5")
      (description "Testpoint 0.8mm X 1.5mm")
      (fields (field (name ".PCBCHECKED") "BP") (field (name ".SCHCHECKED") "BP"))
      (libsource (lib "My Library") (part "Testpoint"))
    )
    (comp (ref "TP2")
      (value "-")
      (footprint "TESTPOINT_0.8X1.5")
      (description "Testpoint 0.8mm X 1.5mm")
      (fields (field (name ".PCBCHECKED") "BP") (field (name ".SCHCHECKED") "BP"))
      (libsource (lib "My Library") (part "Testpoint"))
    )
    (comp (ref "TP3")
      (value "-")
      (footprint "TESTPOINT_0.8X1.5")
      (description "Testpoint 0.8mm X 1.5mm")
      (fields (field (name ".PCBCHECKED") "BP") (field (name ".SCHCHECKED") "BP"))
      (libsource (lib "My Library") (part "Testpoint"))
    )
    (comp (ref "TP4")
      (value "-")
      (footprint "TESTPOINT_0.8X1.5")
      (description "Testpoint 0.8mm X 1.5mm")
      (fields (field (name ".PCBCHECKED") "BP") (field (name ".SCHCHECKED") "BP"))
      (libsource (lib "My Library") (part "Testpoint"))
    )
    (comp (ref "TP5")
      (value "-")
      (footprint "TESTPOINT_0.8X1.5")
      (description "Testpoint 0.8mm X 1.5mm")
      (fields (field (name ".PCBCHECKED") "BP") (field (name ".SCHCHECKED") "BP"))
      (libsource (lib "My Library") (part "Testpoint"))
    )
    (comp (ref "TP6")
      (value "-")
      (footprint "TESTPOINT_0.8X1.5")
      (description "Testpoint 0.8mm X 1.5mm")
      (fields (field (name ".PCBCHECKED") "BP") (field (name ".SCHCHECKED") "BP"))
      (libsource (lib "My Library") (part "Testpoint"))
    )
    (comp (ref "TP7")
      (value "-")
      (footprint "TESTPOINT_0.8X1.5")
      (description "Testpoint 0.8mm X 1.5mm")
      (fields (field (name ".PCBCHECKED") "BP") (field (name ".SCHCHECKED") "BP"))
      (libsource (lib "My Library") (part "Testpoint"))
    )
    (comp (ref "TP8")
      (value "-")
      (footprint "TESTPOINT_0.8X1.5")
      (description "Testpoint 0.8mm X 1.5mm")
      (fields (field (name ".PCBCHECKED") "BP") (field (name ".SCHCHECKED") "BP"))
      (libsource (lib "My Library") (part "Testpoint"))
    )
    (comp (ref "TP9")
      (value "-")
      (footprint "TESTPOINT_0.8X1.5")
      (description "Testpoint 0.8mm X 1.5mm")
      (fields (field (name ".PCBCHECKED") "BP") (field (name ".SCHCHECKED") "BP"))
      (libsource (lib "My Library") (part "Testpoint"))
    )
    (comp (ref "TP10")
      (value "-")
      (footprint "TESTPOINT_0.8X1.5")
      (description "Testpoint 0.8mm X 1.5mm")
      (fields (field (name ".PCBCHECKED") "BP") (field (name ".SCHCHECKED") "BP"))
      (libsource (lib "My Library") (part "Testpoint"))
    )
    (comp (ref "TP11")
      (value "-")
      (footprint "TESTPOINT_0.8X1.5")
      (description "Testpoint 0.8mm X 1.5mm")
      (fields (field (name ".PCBCHECKED") "BP") (field (name ".SCHCHECKED") "BP"))
      (libsource (lib "My Library") (part "Testpoint"))
    )
    (comp (ref "U6")
      (value "INA128UA/2K5")
      (footprint "SOIC8")
      (description "INA128 OP AMP 1.3MHZ SGL 8SOIC")
      (fields (field (name "MANUFACTURER") "Texas Instruments"))
      (libsource (lib "My Library") (part "INA128UA/2K5"))
    )
    (comp (ref "U7")
      (value "INA128UA/2K5")
      (footprint "SOIC8")
      (description "INA128 OP AMP 1.3MHZ SGL 8SOIC")
      (fields (field (name "MANUFACTURER") "Texas Instruments"))
      (libsource (lib "My Library") (part "INA128UA/2K5"))
    )
    (comp (ref "U8")
      (value "INA128UA/2K5")
      (footprint "SOIC8")
      (description "INA128 OP AMP 1.3MHZ SGL 8SOIC")
      (fields (field (name "MANUFACTURER") "Texas Instruments"))
      (libsource (lib "My Library") (part "INA128UA/2K5"))
    )
    (comp (ref "U9")
      (value "INA128UA/2K5")
      (footprint "SOIC8")
      (description "INA128 OP AMP 1.3MHZ SGL 8SOIC")
      (fields (field (name "MANUFACTURER") "Texas Instruments"))
      (libsource (lib "My Library") (part "INA128UA/2K5"))
    )
    (comp (ref "U10")
      (value "AD7732BRUZ")
      (footprint "TSOP65P640X120-28N")
      (description "24 Bit Analog to Digital Converter 2 Input 1 Sigma-Delta 28-TSSOP")
      (libsource (lib "RMOV_chopper") (part "AD7732BRUZ"))
    )
    (comp (ref "U11")
      (value "AD7732BRUZ")
      (footprint "TSOP65P640X120-28N")
      (description "24 Bit Analog to Digital Converter 2 Input 1 Sigma-Delta 28-TSSOP")
      (libsource (lib "RMOV_chopper") (part "AD7732BRUZ"))
    )
    (comp (ref "U12")
      (value "AD7732BRUZ")
      (footprint "TSOP65P640X120-28N")
      (description "24 Bit Analog to Digital Converter 2 Input 1 Sigma-Delta 28-TSSOP")
      (libsource (lib "RMOV_chopper") (part "AD7732BRUZ"))
    )
    (comp (ref "U13")
      (value "INA128UA/2K5")
      (footprint "SOIC8")
      (description "INA128 OP AMP 1.3MHZ SGL 8SOIC")
      (fields (field (name "MANUFACTURER") "Texas Instruments"))
      (libsource (lib "My Library") (part "INA128UA/2K5"))
    )
    (comp (ref "U14")
      (value "INA128UA/2K5")
      (footprint "SOIC8")
      (description "INA128 OP AMP 1.3MHZ SGL 8SOIC")
      (fields (field (name "MANUFACTURER") "Texas Instruments"))
      (libsource (lib "My Library") (part "INA128UA/2K5"))
    )
    (comp (ref "UX1")
      (value "32MHz")
      (footprint "DFN4")
      (description "OSC 32MHZ DFN4 3V3")
      (fields (field (name "MANUFACTURER") "TXC") (field (name "MANUFACTURER PART NUMBER") "7W-32.000MBB-T"))
      (libsource (lib "My Library") (part "7W-32.000MBB-T"))
    )
    (comp (ref "VR1")
      (value "REF3125AIDBZT")
      (footprint "SOT23_123")
      (description "VREF 2.5V SOT23-123")
      (fields (field (name "MANUFACTURER") "Texas Instruments") (field (name "TOLERANCE") "0.2%"))
      (libsource (lib "My Library") (part "REF3125AIDBZT"))
    )
  )
  (nets
    (net (code "1") (name "+12V") (class "Default")
      (node (ref "FB4") (pin "2") (pinfunction "2_2") (pintype "passive"))
    )
    (net (code "2") (name "-12V") (class "Default")
      (node (ref "FB3") (pin "2") (pinfunction "2_2") (pintype "passive"))
    )
    (net (code "3") (name "-12Vm") (class "Default")
      (node (ref "C35") (pin "2") (pinfunction "20_2") (pintype "passive"))
      (node (ref "C41") (pin "2") (pinfunction "20_2") (pintype "passive"))
      (node (ref "C43") (pin "2") (pinfunction "20_2") (pintype "passive"))
      (node (ref "C49") (pin "2") (pinfunction "20_2") (pintype "passive"))
      (node (ref "C70") (pin "1") (pinfunction "1_1") (pintype "passive"))
      (node (ref "C81") (pin "1") (pinfunction "1_1") (pintype "passive"))
      (node (ref "FB3") (pin "1") (pinfunction "1_1") (pintype "passive"))
      (node (ref "TP7") (pin "1") (pinfunction "1_1") (pintype "passive"))
      (node (ref "U13") (pin "4") (pinfunction "-V_4") (pintype "passive"))
      (node (ref "U14") (pin "4") (pinfunction "-V_4") (pintype "passive"))
      (node (ref "U6") (pin "4") (pinfunction "-V_4") (pintype "passive"))
      (node (ref "U7") (pin "4") (pinfunction "-V_4") (pintype "passive"))
      (node (ref "U8") (pin "4") (pinfunction "-V_4") (pintype "passive"))
      (node (ref "U9") (pin "4") (pinfunction "-V_4") (pintype "passive"))
    )
    (net (code "4") (name "/2.5Vref") (class "Default")
      (node (ref "C68") (pin "2") (pinfunction "20_2") (pintype "passive"))
      (node (ref "U10") (pin "11") (pinfunction "BIAS1+_11") (pintype "passive"))
      (node (ref "U10") (pin "14") (pinfunction "BIAS0+_14") (pintype "passive"))
      (node (ref "U10") (pin "15") (pinfunction "BIAS0-_15") (pintype "passive"))
      (node (ref "U10") (pin "18") (pinfunction "BIAS1-_18") (pintype "passive"))
      (node (ref "U10") (pin "21") (pinfunction "REFIN+_21") (pintype "passive"))
      (node (ref "U11") (pin "11") (pinfunction "BIAS1+_11") (pintype "passive"))
      (node (ref "U11") (pin "14") (pinfunction "BIAS0+_14") (pintype "passive"))
      (node (ref "U11") (pin "15") (pinfunction "BIAS0-_15") (pintype "passive"))
      (node (ref "U11") (pin "18") (pinfunction "BIAS1-_18") (pintype "passive"))
      (node (ref "U11") (pin "21") (pinfunction "REFIN+_21") (pintype "passive"))
      (node (ref "U12") (pin "11") (pinfunction "BIAS1+_11") (pintype "passive"))
      (node (ref "U12") (pin "14") (pinfunction "BIAS0+_14") (pintype "passive"))
      (node (ref "U12") (pin "15") (pinfunction "BIAS0-_15") (pintype "passive"))
      (node (ref "U12") (pin "18") (pinfunction "BIAS1-_18") (pintype "passive"))
      (node (ref "U12") (pin "21") (pinfunction "REFIN+_21") (pintype "passive"))
      (node (ref "VR1") (pin "2") (pinfunction "Ref_2") (pintype "passive"))
    )
    (net (code "5") (name "/MCLK") (class "Default")
      (node (ref "R71") (pin "1") (pinfunction "1_1") (pintype "passive"))
      (node (ref "R76") (pin "1") (pinfunction "1_1") (pintype "passive"))
      (node (ref "R83") (pin "2") (pinfunction "2_2") (pintype "passive"))
      (node (ref "U10") (pin "2") (pinfunction "MCLKIN_2") (pintype "passive"))
      (node (ref "U11") (pin "2") (pinfunction "MCLKIN_2") (pintype "passive"))
      (node (ref "U12") (pin "2") (pinfunction "MCLKIN_2") (pintype "passive"))
      (node (ref "UX1") (pin "3") (pinfunction "OUT_3") (pintype "passive"))
    )
    (net (code "6") (name "3.3Vm") (class "Default")
      (node (ref "C63") (pin "1") (pinfunction "1_1") (pintype "passive"))
      (node (ref "C65") (pin "1") (pinfunction "1_1") (pintype "passive"))
      (node (ref "C69") (pin "2") (pinfunction "20_2") (pintype "passive"))
      (node (ref "C75") (pin "1") (pinfunction "1_1") (pintype "passive"))
      (node (ref "FB1") (pin "1") (pinfunction "1_1") (pintype "passive"))
      (node (ref "R70") (pin "2") (pinfunction "2_2") (pintype "passive"))
      (node (ref "R71") (pin "2") (pinfunction "2_2") (pintype "passive"))
      (node (ref "R72") (pin "1") (pinfunction "1_1") (pintype "passive"))
      (node (ref "R73") (pin "1") (pinfunction "1_1") (pintype "passive"))
      (node (ref "R75") (pin "2") (pinfunction "2_2") (pintype "passive"))
      (node (ref "R76") (pin "2") (pinfunction "2_2") (pintype "passive"))
      (node (ref "R77") (pin "1") (pinfunction "1_1") (pintype "passive"))
      (node (ref "R78") (pin "1") (pinfunction "1_1") (pintype "passive"))
      (node (ref "R81") (pin "1") (pinfunction "1_1") (pintype "passive"))
      (node (ref "R83") (pin "1") (pinfunction "1_1") (pintype "passive"))
      (node (ref "R86") (pin "1") (pinfunction "1_1") (pintype "passive"))
      (node (ref "R87") (pin "2") (pinfunction "2_2") (pintype "passive"))
      (node (ref "TP4") (pin "1") (pinfunction "1_1") (pintype "passive"))
      (node (ref "U10") (pin "27") (pinfunction "DVdd_27") (pintype "passive"))
      (node (ref "U11") (pin "27") (pinfunction "DVdd_27") (pintype "passive"))
      (node (ref "U12") (pin "27") (pinfunction "DVdd_27") (pintype "passive"))
      (node (ref "UX1") (pin "1") (pinfunction "EN_1") (pintype "passive"))
      (node (ref "UX1") (pin "4") (pinfunction "VDD_4") (pintype "passive"))
    )
    (net (code "7") (name "3V3") (class "Default")
      (node (ref "FB1") (pin "2") (pinfunction "2_2") (pintype "passive"))
    )
    (net (code "8") (name "5V") (class "Default")
      (node (ref "FB2") (pin "2") (pinfunction "2_2") (pintype "passive"))
    )
    (net (code "9") (name "5Vm") (class "Default")
      (node (ref "C64") (pin "2") (pinfunction "20_2") (pintype "passive"))
      (node (ref "C66") (pin "2") (pinfunction "20_2") (pintype "passive"))
      (node (ref "C67") (pin "2") (pinfunction "20_2") (pintype "passive"))
      (node (ref "C79") (pin "2") (pinfunction "20_2") (pintype "passive"))
      (node (ref "FB2") (pin "1") (pinfunction "1_1") (pintype "passive"))
      (node (ref "TP6") (pin "1") (pinfunction "1_1") (pintype "passive"))
      (node (ref "U10") (pin "6") (pinfunction "AVdd_6") (pintype "passive"))
      (node (ref "U11") (pin "6") (pinfunction "AVdd_6") (pintype "passive"))
      (node (ref "U12") (pin "6") (pinfunction "AVdd_6") (pintype "passive"))
      (node (ref "VR1") (pin "1") (pinfunction "Vin_1") (pintype "passive"))
    )
    (net (code "10") (name "12Vm") (class "Default")
      (node (ref "C39") (pin "2") (pinfunction "20_2") (pintype "passive"))
      (node (ref "C42") (pin "2") (pinfunction "20_2") (pintype "passive"))
      (node (ref "C47") (pin "2") (pinfunction "20_2") (pintype "passive"))
      (node (ref "C50") (pin "2") (pinfunction "20_2") (pintype "passive"))
      (node (ref "C77") (pin "1") (pinfunction "1_1") (pintype "passive"))
      (node (ref "C85") (pin "1") (pinfunction "1_1") (pintype "passive"))
      (node (ref "FB4") (pin "1") (pinfunction "1_1") (pintype "passive"))
      (node (ref "TP8") (pin "1") (pinfunction "1_1") (pintype "passive"))
      (node (ref "U13") (pin "7") (pinfunction "+V_7") (pintype "passive"))
      (node (ref "U14") (pin "7") (pinfunction "+V_7") (pintype "passive"))
      (node (ref "U6") (pin "7") (pinfunction "+V_7") (pintype "passive"))
      (node (ref "U7") (pin "7") (pinfunction "+V_7") (pintype "passive"))
      (node (ref "U8") (pin "7") (pinfunction "+V_7") (pintype "passive"))
      (node (ref "U9") (pin "7") (pinfunction "+V_7") (pintype "passive"))
    )
    (net (code "11") (name "A_GND") (class "Default")
      (node (ref "C35") (pin "1") (pinfunction "1_1") (pintype "passive"))
      (node (ref "C39") (pin "1") (pinfunction "1_1") (pintype "passive"))
      (node (ref "C41") (pin "1") (pinfunction "1_1") (pintype "passive"))
      (node (ref "C42") (pin "1") (pinfunction "1_1") (pintype "passive"))
      (node (ref "C43") (pin "1") (pinfunction "1_1") (pintype "passive"))
      (node (ref "C47") (pin "1") (pinfunction "1_1") (pintype "passive"))
      (node (ref "C49") (pin "1") (pinfunction "1_1") (pintype "passive"))
      (node (ref "C50") (pin "1") (pinfunction "1_1") (pintype "passive"))
      (node (ref "C51") (pin "1") (pinfunction "1_1") (pintype "passive"))
      (node (ref "C52") (pin "1") (pinfunction "1_1") (pintype "passive"))
      (node (ref "C53") (pin "1") (pinfunction "1_1") (pintype "passive"))
      (node (ref "C54") (pin "1") (pinfunction "1_1") (pintype "passive"))
      (node (ref "C55") (pin "1") (pinfunction "1_1") (pintype "passive"))
      (node (ref "C56") (pin "1") (pinfunction "1_1") (pintype "passive"))
      (node (ref "C57") (pin "1") (pinfunction "1_1") (pintype "passive"))
      (node (ref "C58") (pin "1") (pinfunction "1_1") (pintype "passive"))
      (node (ref "C59") (pin "1") (pinfunction "1_1") (pintype "passive"))
      (node (ref "C60") (pin "1") (pinfunction "1_1") (pintype "passive"))
      (node (ref "C61") (pin "1") (pinfunction "1_1") (pintype "passive"))
      (node (ref "C62") (pin "1") (pinfunction "1_1") (pintype "passive"))
      (node (ref "C64") (pin "1") (pinfunction "1_1") (pintype "passive"))
      (node (ref "C66") (pin "1") (pinfunction "1_1") (pintype "passive"))
      (node (ref "C67") (pin "1") (pinfunction "1_1") (pintype "passive"))
      (node (ref "C68") (pin "1") (pinfunction "1_1") (pintype "passive"))
      (node (ref "C70") (pin "2") (pinfunction "20_2") (pintype "passive"))
      (node (ref "C71") (pin "2") (pinfunction "20_2") (pintype "passive"))
      (node (ref "C76") (pin "1") (pinfunction "1_1") (pintype "passive"))
      (node (ref "C77") (pin "2") (pinfunction "20_2") (pintype "passive"))
      (node (ref "C78") (pin "2") (pinfunction "20_2") (pintype "passive"))
      (node (ref "C79") (pin "1") (pinfunction "1_1") (pintype "passive"))
      (node (ref "C80") (pin "2") (pinfunction "20_2") (pintype "passive"))
      (node (ref "C81") (pin "2") (pinfunction "20_2") (pintype "passive"))
      (node (ref "C83") (pin "1") (pinfunction "1_1") (pintype "passive"))
      (node (ref "C84") (pin "2") (pinfunction "20_2") (pintype "passive"))
      (node (ref "C85") (pin "2") (pinfunction "20_2") (pintype "passive"))
      (node (ref "R58") (pin "2") (pinfunction "2_2") (pintype "passive"))
      (node (ref "R64") (pin "2") (pinfunction "2_2") (pintype "passive"))
      (node (ref "U10") (pin "16") (pinfunction "AIN0-_16") (pintype "passive"))
      (node (ref "U10") (pin "17") (pinfunction "AIN1-_17") (pintype "passive"))
      (node (ref "U10") (pin "22") (pinfunction "REFIN-_22") (pintype "passive"))
      (node (ref "U10") (pin "23") (pinfunction "AGND_23") (pintype "passive"))
      (node (ref "U11") (pin "16") (pinfunction "AIN0-_16") (pintype "passive"))
      (node (ref "U11") (pin "17") (pinfunction "AIN1-_17") (pintype "passive"))
      (node (ref "U11") (pin "22") (pinfunction "REFIN-_22") (pintype "passive"))
      (node (ref "U11") (pin "23") (pinfunction "AGND_23") (pintype "passive"))
      (node (ref "U12") (pin "16") (pinfunction "AIN0-_16") (pintype "passive"))
      (node (ref "U12") (pin "17") (pinfunction "AIN1-_17") (pintype "passive"))
      (node (ref "U12") (pin "22") (pinfunction "REFIN-_22") (pintype "passive"))
      (node (ref "U12") (pin "23") (pinfunction "AGND_23") (pintype "passive"))
      (node (ref "U13") (pin "5") (pinfunction "REF_5") (pintype "passive"))
      (node (ref "U14") (pin "5") (pinfunction "REF_5") (pintype "passive"))
      (node (ref "U6") (pin "5") (pinfunction "REF_5") (pintype "passive"))
      (node (ref "U7") (pin "5") (pinfunction "REF_5") (pintype "passive"))
      (node (ref "U8") (pin "5") (pinfunction "REF_5") (pintype "passive"))
      (node (ref "U9") (pin "5") (pinfunction "REF_5") (pintype "passive"))
      (node (ref "VR1") (pin "3") (pinfunction "GND_3") (pintype "passive"))
    )
    (net (code "12") (name "CSa") (class "Default")
      (node (ref "R72") (pin "2") (pinfunction "2_2") (pintype "passive"))
      (node (ref "U10") (pin "4") (pinfunction "~{CS}_4") (pintype "passive"))
    )
    (net (code "13") (name "CSb") (class "Default")
      (node (ref "R77") (pin "2") (pinfunction "2_2") (pintype "passive"))
      (node (ref "U11") (pin "4") (pinfunction "~{CS}_4") (pintype "passive"))
    )
    (net (code "14") (name "CSc") (class "Default")
      (node (ref "R86") (pin "2") (pinfunction "2_2") (pintype "passive"))
      (node (ref "U12") (pin "4") (pinfunction "~{CS}_4") (pintype "passive"))
    )
    (net (code "15") (name "DIN") (class "Default")
      (node (ref "U10") (pin "26") (pinfunction "DIN_26") (pintype "passive"))
      (node (ref "U11") (pin "26") (pinfunction "DIN_26") (pintype "passive"))
      (node (ref "U12") (pin "26") (pinfunction "DIN_26") (pintype "passive"))
    )
    (net (code "16") (name "DOUT") (class "Default")
      (node (ref "U10") (pin "25") (pinfunction "DOUT_25") (pintype "passive"))
      (node (ref "U11") (pin "25") (pinfunction "DOUT_25") (pintype "passive"))
      (node (ref "U12") (pin "25") (pinfunction "DOUT_25") (pintype "passive"))
    )
    (net (code "17") (name "D_GND") (class "Default")
      (node (ref "C63") (pin "2") (pinfunction "20_2") (pintype "passive"))
      (node (ref "C65") (pin "2") (pinfunction "20_2") (pintype "passive"))
      (node (ref "C69") (pin "1") (pinfunction "1_1") (pintype "passive"))
      (node (ref "C75") (pin "2") (pinfunction "20_2") (pintype "passive"))
      (node (ref "R65") (pin "1") (pinfunction "1_1") (pintype "passive"))
      (node (ref "TP9") (pin "1") (pinfunction "1_1") (pintype "passive"))
      (node (ref "U10") (pin "28") (pinfunction "DGND_28") (pintype "passive"))
      (node (ref "U11") (pin "28") (pinfunction "DGND_28") (pintype "passive"))
      (node (ref "U12") (pin "28") (pinfunction "DGND_28") (pintype "passive"))
      (node (ref "UX1") (pin "2") (pinfunction "GND_2") (pintype "passive"))
    )
    (net (code "18") (name "EARTH") (class "Default")
      (node (ref "C36") (pin "2") (pinfunction "2_2") (pintype "passive"))
      (node (ref "C40") (pin "2") (pinfunction "2_2") (pintype "passive"))
      (node (ref "C44") (pin "2") (pinfunction "2_2") (pintype "passive"))
      (node (ref "C48") (pin "1") (pinfunction "1_1") (pintype "passive"))
    )
    (net (code "19") (name "KONVa") (class "Default")
      (node (ref "R73") (pin "2") (pinfunction "2_2") (pintype "passive"))
      (node (ref "U10") (pin "24") (pinfunction "~{RDY}_24") (pintype "passive"))
    )
    (net (code "20") (name "KONVb") (class "Default")
      (node (ref "R78") (pin "2") (pinfunction "2_2") (pintype "passive"))
      (node (ref "U11") (pin "24") (pinfunction "~{RDY}_24") (pintype "passive"))
    )
    (net (code "21") (name "KONVc") (class "Default")
      (node (ref "R87") (pin "1") (pinfunction "1_1") (pintype "passive"))
      (node (ref "U12") (pin "24") (pinfunction "~{RDY}_24") (pintype "passive"))
    )
    (net (code "22") (name "Net-(C38-20)") (class "Default")
      (node (ref "C38") (pin "2") (pinfunction "20_2") (pintype "passive"))
      (node (ref "LF1") (pin "4") (pinfunction "4_4") (pintype "passive"))
      (node (ref "R47") (pin "2") (pinfunction "2_2") (pintype "passive"))
      (node (ref "R49") (pin "1") (pinfunction "1_1") (pintype "passive"))
      (node (ref "R52") (pin "1") (pinfunction "1_1") (pintype "passive"))
    )
    (net (code "23") (name "Net-(C38-Pad1)") (class "Default")
      (node (ref "C38") (pin "1") (pinfunction "1_1") (pintype "passive"))
      (node (ref "LF1") (pin "3") (pinfunction "3_3") (pintype "passive"))
      (node (ref "R47") (pin "1") (pinfunction "1_1") (pintype "passive"))
      (node (ref "R51") (pin "1") (pinfunction "1_1") (pintype "passive"))
      (node (ref "R54") (pin "1") (pinfunction "1_1") (pintype "passive"))
    )
    (net (code "24") (name "Net-(C45-20)") (class "Default")
      (node (ref "C44") (pin "1") (pinfunction "1_1") (pintype "passive"))
      (node (ref "C45") (pin "2") (pinfunction "20_2") (pintype "passive"))
      (node (ref "J1") (pin "1") (pinfunction "1_1") (pintype "passive"))
      (node (ref "LF2") (pin "1") (pinfunction "1_1") (pintype "passive"))
      (node (ref "RV1") (pin "2") (pinfunction "2_2") (pintype "passive"))
    )
    (net (code "25") (name "Net-(C45-Pad1)") (class "Default")
      (node (ref "C45") (pin "1") (pinfunction "1_1") (pintype "passive"))
      (node (ref "C48") (pin "2") (pinfunction "2_2") (pintype "passive"))
      (node (ref "J2") (pin "1") (pinfunction "1_1") (pintype "passive"))
      (node (ref "LF2") (pin "2") (pinfunction "2_2") (pintype "passive"))
      (node (ref "RV1") (pin "1") (pinfunction "1_1") (pintype "passive"))
    )
    (net (code "26") (name "Net-(C46-20)") (class "Default")
      (node (ref "C46") (pin "2") (pinfunction "20_2") (pintype "passive"))
      (node (ref "LF2") (pin "4") (pinfunction "4_4") (pintype "passive"))
      (node (ref "R48") (pin "2") (pinfunction "2_2") (pintype "passive"))
      (node (ref "R55") (pin "1") (pinfunction "1_1") (pintype "passive"))
      (node (ref "R61") (pin "1") (pinfunction "1_1") (pintype "passive"))
    )
    (net (code "27") (name "Net-(C46-Pad1)") (class "Default")
      (node (ref "C46") (pin "1") (pinfunction "1_1") (pintype "passive"))
      (node (ref "LF2") (pin "3") (pinfunction "3_3") (pintype "passive"))
      (node (ref "R48") (pin "1") (pinfunction "1_1") (pintype "passive"))
      (node (ref "R57") (pin "1") (pinfunction "1_1") (pintype "passive"))
      (node (ref "R63") (pin "1") (pinfunction "1_1") (pintype "passive"))
    )
    (net (code "28") (name "Net-(C52-20)") (class "Default")
      (node (ref "C52") (pin "2") (pinfunction "20_2") (pintype "passive"))
      (node (ref "R50") (pin "2") (pinfunction "2_2") (pintype "passive"))
      (node (ref "TP1") (pin "1") (pinfunction "1_1") (pintype "passive"))
      (node (ref "U10") (pin "12") (pinfunction "AIN1+_12") (pintype "passive"))
    )
    (net (code "29") (name "Net-(C56-20)") (class "Default")
      (node (ref "C56") (pin "2") (pinfunction "20_2") (pintype "passive"))
      (node (ref "R53") (pin "2") (pinfunction "2_2") (pintype "passive"))
      (node (ref "TP2") (pin "1") (pinfunction "1_1") (pintype "passive"))
      (node (ref "U10") (pin "13") (pinfunction "AIN0+_13") (pintype "passive"))
    )
    (net (code "30") (name "Net-(C58-20)") (class "Default")
      (node (ref "C58") (pin "2") (pinfunction "20_2") (pintype "passive"))
      (node (ref "R56") (pin "2") (pinfunction "2_2") (pintype "passive"))
      (node (ref "TP3") (pin "1") (pinfunction "1_1") (pintype "passive"))
      (node (ref "U11") (pin "12") (pinfunction "AIN1+_12") (pintype "passive"))
    )
    (net (code "31") (name "Net-(C61-20)") (class "Default")
      (node (ref "C61") (pin "2") (pinfunction "20_2") (pintype "passive"))
      (node (ref "R62") (pin "2") (pinfunction "2_2") (pintype "passive"))
      (node (ref "TP5") (pin "1") (pinfunction "1_1") (pintype "passive"))
      (node (ref "U11") (pin "13") (pinfunction "AIN0+_13") (pintype "passive"))
    )
    (net (code "32") (name "Net-(C72-20)") (class "Default")
      (node (ref "C72") (pin "2") (pinfunction "20_2") (pintype "passive"))
      (node (ref "J3") (pin "1") (pinfunction "1_1") (pintype "passive"))
      (node (ref "LF3") (pin "1") (pinfunction "1_1") (pintype "passive"))
    )
    (net (code "33") (name "Net-(C72-Pad1)") (class "Default")
      (node (ref "C72") (pin "1") (pinfunction "1_1") (pintype "passive"))
      (node (ref "J4") (pin "1") (pinfunction "1_1") (pintype "passive"))
      (node (ref "LF3") (pin "2") (pinfunction "2_2") (pintype "passive"))
    )
    (net (code "34") (name "Net-(C73-20)") (class "Default")
      (node (ref "C73") (pin "2") (pinfunction "20_2") (pintype "passive"))
      (node (ref "LF3") (pin "4") (pinfunction "4_4") (pintype "passive"))
      (node (ref "R80") (pin "1") (pinfunction "1_1") (pintype "passive"))
      (node (ref "R84") (pin "2") (pinfunction "2_2") (pintype "passive"))
      (node (ref "R93") (pin "1") (pinfunction "1_1") (pintype "passive"))
    )
    (net (code "35") (name "Net-(C73-Pad1)") (class "Default")
      (node (ref "C73") (pin "1") (pinfunction "1_1") (pintype "passive"))
      (node (ref "LF3") (pin "3") (pinfunction "3_3") (pintype "passive"))
      (node (ref "R84") (pin "1") (pinfunction "1_1") (pintype "passive"))
      (node (ref "R85") (pin "1") (pinfunction "1_1") (pintype "passive"))
      (node (ref "R91") (pin "1") (pinfunction "1_1") (pintype "passive"))
    )
    (net (code "36") (name "Net-(C74-20)") (class "Default")
      (node (ref "C71") (pin "1") (pinfunction "1_1") (pintype "passive"))
      (node (ref "C74") (pin "2") (pinfunction "20_2") (pintype "passive"))
      (node (ref "R80") (pin "2") (pinfunction "2_2") (pintype "passive"))
      (node (ref "U13") (pin "2") (pinfunction "VIN-_2") (pintype "passive"))
    )
    (net (code "37") (name "Net-(C76-20)") (class "Default")
      (node (ref "C76") (pin "2") (pinfunction "20_2") (pintype "passive"))
      (node (ref "R82") (pin "2") (pinfunction "2_2") (pintype "passive"))
      (node (ref "TP10") (pin "1") (pinfunction "1_1") (pintype "passive"))
      (node (ref "U12") (pin "12") (pinfunction "AIN1+_12") (pintype "passive"))
    )
    (net (code "38") (name "Net-(C82-20)") (class "Default")
      (node (ref "C80") (pin "1") (pinfunction "1_1") (pintype "passive"))
      (node (ref "C82") (pin "2") (pinfunction "20_2") (pintype "passive"))
      (node (ref "R91") (pin "2") (pinfunction "2_2") (pintype "passive"))
      (node (ref "U14") (pin "2") (pinfunction "VIN-_2") (pintype "passive"))
    )
    (net (code "39") (name "Net-(C83-20)") (class "Default")
      (node (ref "C83") (pin "2") (pinfunction "20_2") (pintype "passive"))
      (node (ref "R92") (pin "2") (pinfunction "2_2") (pintype "passive"))
      (node (ref "TP11") (pin "1") (pinfunction "1_1") (pintype "passive"))
      (node (ref "U12") (pin "13") (pinfunction "AIN0+_13") (pintype "passive"))
    )
    (net (code "40") (name "Net-(R66-Pad1)") (class "Default")
      (node (ref "R66") (pin "1") (pinfunction "1_1") (pintype "passive"))
      (node (ref "U6") (pin "1") (pinfunction "RG_1") (pintype "passive"))
    )
    (net (code "41") (name "Net-(R66-Pad2)") (class "Default")
      (node (ref "R66") (pin "2") (pinfunction "2_2") (pintype "passive"))
      (node (ref "U6") (pin "8") (pinfunction "RG_8") (pintype "passive"))
    )
    (net (code "42") (name "Net-(R67-Pad1)") (class "Default")
      (node (ref "R67") (pin "1") (pinfunction "1_1") (pintype "passive"))
      (node (ref "U7") (pin "1") (pinfunction "RG_1") (pintype "passive"))
    )
    (net (code "43") (name "Net-(R67-Pad2)") (class "Default")
      (node (ref "R67") (pin "2") (pinfunction "2_2") (pintype "passive"))
      (node (ref "U7") (pin "8") (pinfunction "RG_8") (pintype "passive"))
    )
    (net (code "44") (name "Net-(R68-Pad1)") (class "Default")
      (node (ref "R68") (pin "1") (pinfunction "1_1") (pintype "passive"))
      (node (ref "U8") (pin "1") (pinfunction "RG_1") (pintype "passive"))
    )
    (net (code "45") (name "Net-(R68-Pad2)") (class "Default")
      (node (ref "R68") (pin "2") (pinfunction "2_2") (pintype "passive"))
      (node (ref "U8") (pin "8") (pinfunction "RG_8") (pintype "passive"))
    )
    (net (code "46") (name "Net-(R94-Pad1)") (class "Default")
      (node (ref "R94") (pin "1") (pinfunction "1_1") (pintype "passive"))
      (node (ref "U13") (pin "1") (pinfunction "RG_1") (pintype "passive"))
    )
    (net (code "47") (name "Net-(R94-Pad2)") (class "Default")
      (node (ref "R94") (pin "2") (pinfunction "2_2") (pintype "passive"))
      (node (ref "U13") (pin "8") (pinfunction "RG_8") (pintype "passive"))
    )
    (net (code "48") (name "Net-(R95-Pad1)") (class "Default")
      (node (ref "R95") (pin "1") (pinfunction "1_1") (pintype "passive"))
      (node (ref "U14") (pin "1") (pinfunction "RG_1") (pintype "passive"))
    )
    (net (code "49") (name "Net-(R95-Pad2)") (class "Default")
      (node (ref "R95") (pin "2") (pinfunction "2_2") (pintype "passive"))
      (node (ref "U14") (pin "8") (pinfunction "RG_8") (pintype "passive"))
    )
    (net (code "50") (name "Net-(U6-VIN-)") (class "Default")
      (node (ref "C51") (pin "2") (pinfunction "2_2") (pintype "passive"))
      (node (ref "R49") (pin "2") (pinfunction "2_2") (pintype "passive"))
      (node (ref "U6") (pin "2") (pinfunction "VIN-_2") (pintype "passive"))
    )
    (net (code "51") (name "Net-(U6-Vin+)") (class "Default")
      (node (ref "C53") (pin "2") (pinfunction "2_2") (pintype "passive"))
      (node (ref "R51") (pin "2") (pinfunction "2_2") (pintype "passive"))
      (node (ref "U6") (pin "3") (pinfunction "Vin+_3") (pintype "passive"))
    )
    (net (code "52") (name "Net-(U6-Vout)") (class "Default")
      (node (ref "R50") (pin "1") (pinfunction "1_1") (pintype "passive"))
      (node (ref "U6") (pin "6") (pinfunction "Vout_6") (pintype "passive"))
    )
    (net (code "53") (name "Net-(U7-VIN-)") (class "Default")
      (node (ref "C54") (pin "2") (pinfunction "2_2") (pintype "passive"))
      (node (ref "R52") (pin "2") (pinfunction "2_2") (pintype "passive"))
      (node (ref "U7") (pin "2") (pinfunction "VIN-_2") (pintype "passive"))
    )
    (net (code "54") (name "Net-(U7-Vin+)") (class "Default")
      (node (ref "C55") (pin "2") (pinfunction "2_2") (pintype "passive"))
      (node (ref "R54") (pin "2") (pinfunction "2_2") (pintype "passive"))
      (node (ref "U7") (pin "3") (pinfunction "Vin+_3") (pintype "passive"))
    )
    (net (code "55") (name "Net-(U7-Vout)") (class "Default")
      (node (ref "R53") (pin "1") (pinfunction "1_1") (pintype "passive"))
      (node (ref "U7") (pin "6") (pinfunction "Vout_6") (pintype "passive"))
    )
    (net (code "56") (name "Net-(U8-VIN-)") (class "Default")
      (node (ref "C57") (pin "2") (pinfunction "2_2") (pintype "passive"))
      (node (ref "R55") (pin "2") (pinfunction "2_2") (pintype "passive"))
      (node (ref "U8") (pin "2") (pinfunction "VIN-_2") (pintype "passive"))
    )
    (net (code "57") (name "Net-(U8-Vin+)") (class "Default")
      (node (ref "C59") (pin "2") (pinfunction "2_2") (pintype "passive"))
      (node (ref "R57") (pin "2") (pinfunction "2_2") (pintype "passive"))
      (node (ref "U8") (pin "3") (pinfunction "Vin+_3") (pintype "passive"))
    )
    (net (code "58") (name "Net-(U8-Vout)") (class "Default")
      (node (ref "R56") (pin "1") (pinfunction "1_1") (pintype "passive"))
      (node (ref "U8") (pin "6") (pinfunction "Vout_6") (pintype "passive"))
    )
    (net (code "59") (name "Net-(U9-VIN-)") (class "Default")
      (node (ref "C60") (pin "2") (pinfunction "2_2") (pintype "passive"))
      (node (ref "R58") (pin "1") (pinfunction "1_1") (pintype "passive"))
      (node (ref "R61") (pin "2") (pinfunction "2_2") (pintype "passive"))
      (node (ref "U9") (pin "2") (pinfunction "VIN-_2") (pintype "passive"))
    )
    (net (code "60") (name "Net-(U9-Vin+)") (class "Default")
      (node (ref "C62") (pin "2") (pinfunction "2_2") (pintype "passive"))
      (node (ref "R63") (pin "2") (pinfunction "2_2") (pintype "passive"))
      (node (ref "R64") (pin "1") (pinfunction "1_1") (pintype "passive"))
      (node (ref "U9") (pin "3") (pinfunction "Vin+_3") (pintype "passive"))
    )
    (net (code "61") (name "Net-(U9-Vout)") (class "Default")
      (node (ref "R62") (pin "1") (pinfunction "1_1") (pintype "passive"))
      (node (ref "U9") (pin "6") (pinfunction "Vout_6") (pintype "passive"))
    )
    (net (code "62") (name "Net-(U10-~{SYNC}{slash}P1)") (class "Default")
      (node (ref "R74") (pin "2") (pinfunction "2_2") (pintype "passive"))
      (node (ref "U10") (pin "8") (pinfunction "~{SYNC}/P1_8") (pintype "passive"))
    )
    (net (code "63") (name "Net-(U11-~{SYNC}{slash}P1)") (class "Default")
      (node (ref "R79") (pin "2") (pinfunction "2_2") (pintype "passive"))
      (node (ref "U11") (pin "8") (pinfunction "~{SYNC}/P1_8") (pintype "passive"))
    )
    (net (code "64") (name "Net-(U12-~{SYNC}{slash}P1)") (class "Default")
      (node (ref "R88") (pin "2") (pinfunction "2_2") (pintype "passive"))
      (node (ref "U12") (pin "8") (pinfunction "~{SYNC}/P1_8") (pintype "passive"))
    )
    (net (code "65") (name "Net-(U13-Vin+)") (class "Default")
      (node (ref "C74") (pin "1") (pinfunction "1_1") (pintype "passive"))
      (node (ref "C78") (pin "1") (pinfunction "1_1") (pintype "passive"))
      (node (ref "R85") (pin "2") (pinfunction "2_2") (pintype "passive"))
      (node (ref "U13") (pin "3") (pinfunction "Vin+_3") (pintype "passive"))
    )
    (net (code "66") (name "Net-(U13-Vout)") (class "Default")
      (node (ref "R82") (pin "1") (pinfunction "1_1") (pintype "passive"))
      (node (ref "U13") (pin "6") (pinfunction "Vout_6") (pintype "passive"))
    )
    (net (code "67") (name "Net-(U14-Vin+)") (class "Default")
      (node (ref "C82") (pin "1") (pinfunction "1_1") (pintype "passive"))
      (node (ref "C84") (pin "1") (pinfunction "1_1") (pintype "passive"))
      (node (ref "R93") (pin "2") (pinfunction "2_2") (pintype "passive"))
      (node (ref "U14") (pin "3") (pinfunction "Vin+_3") (pintype "passive"))
    )
    (net (code "68") (name "Net-(U14-Vout)") (class "Default")
      (node (ref "R92") (pin "1") (pinfunction "1_1") (pintype "passive"))
      (node (ref "U14") (pin "6") (pinfunction "Vout_6") (pintype "passive"))
    )
    (net (code "69") (name "P_GND") (class "Default")
      (node (ref "R65") (pin "2") (pinfunction "2_2") (pintype "passive"))
    )
    (net (code "70") (name "R_ADC") (class "Default")
      (node (ref "U10") (pin "5") (pinfunction "~{RESET}_5") (pintype "passive"))
      (node (ref "U11") (pin "5") (pinfunction "~{RESET}_5") (pintype "passive"))
      (node (ref "U12") (pin "5") (pinfunction "~{RESET}_5") (pintype "passive"))
    )
    (net (code "71") (name "SCLK") (class "Default")
      (node (ref "R70") (pin "1") (pinfunction "1_1") (pintype "passive"))
      (node (ref "R75") (pin "1") (pinfunction "1_1") (pintype "passive"))
      (node (ref "R81") (pin "2") (pinfunction "2_2") (pintype "passive"))
      (node (ref "U10") (pin "1") (pinfunction "SCLK_1") (pintype "passive"))
      (node (ref "U11") (pin "1") (pinfunction "SCLK_1") (pintype "passive"))
      (node (ref "U12") (pin "1") (pinfunction "SCLK_1") (pintype "passive"))
    )
    (net (code "72") (name "Shunt+") (class "Default")
      (node (ref "C37") (pin "1") (pinfunction "1_1") (pintype "passive"))
      (node (ref "C40") (pin "1") (pinfunction "1_1") (pintype "passive"))
      (node (ref "LF1") (pin "2") (pinfunction "2_2") (pintype "passive"))
    )
    (net (code "73") (name "Shunt-") (class "Default")
      (node (ref "C36") (pin "1") (pinfunction "1_1") (pintype "passive"))
      (node (ref "C37") (pin "2") (pinfunction "20_2") (pintype "passive"))
      (node (ref "LF1") (pin "1") (pinfunction "1_1") (pintype "passive"))
    )
    (net (code "74") (name "Sync") (class "Default")
      (node (ref "R74") (pin "1") (pinfunction "1_1") (pintype "passive"))
      (node (ref "R79") (pin "1") (pinfunction "1_1") (pintype "passive"))
      (node (ref "R88") (pin "1") (pinfunction "1_1") (pintype "passive"))
    )
    (net (code "75") (name "unconnected-(U9-RG-Pad1)") (class "Default")
      (node (ref "U9") (pin "1") (pinfunction "RG_1") (pintype "passive"))
    )
    (net (code "76") (name "unconnected-(U9-RG-Pad8)") (class "Default")
      (node (ref "U9") (pin "8") (pinfunction "RG_8") (pintype "passive"))
    )
    (net (code "77") (name "unconnected-(U10-MCLKOUT-Pad3)") (class "Default")
      (node (ref "U10") (pin "3") (pinfunction "MCLKOUT_3") (pintype "passive"))
    )
    (net (code "78") (name "unconnected-(U10-P0-Pad7)") (class "Default")
      (node (ref "U10") (pin "7") (pinfunction "P0_7") (pintype "passive"))
    )
    (net (code "79") (name "unconnected-(U10-RA-Pad9)") (class "Default")
      (node (ref "U10") (pin "9") (pinfunction "RA_9") (pintype "passive"))
    )
    (net (code "80") (name "unconnected-(U10-RB-Pad10)") (class "Default")
      (node (ref "U10") (pin "10") (pinfunction "RB_10") (pintype "passive"))
    )
    (net (code "81") (name "unconnected-(U10-RC-Pad19)") (class "Default")
      (node (ref "U10") (pin "19") (pinfunction "RC_19") (pintype "passive"))
    )
    (net (code "82") (name "unconnected-(U10-RD-Pad20)") (class "Default")
      (node (ref "U10") (pin "20") (pinfunction "RD_20") (pintype "passive"))
    )
    (net (code "83") (name "unconnected-(U11-MCLKOUT-Pad3)") (class "Default")
      (node (ref "U11") (pin "3") (pinfunction "MCLKOUT_3") (pintype "passive"))
    )
    (net (code "84") (name "unconnected-(U11-P0-Pad7)") (class "Default")
      (node (ref "U11") (pin "7") (pinfunction "P0_7") (pintype "passive"))
    )
    (net (code "85") (name "unconnected-(U11-RA-Pad9)") (class "Default")
      (node (ref "U11") (pin "9") (pinfunction "RA_9") (pintype "passive"))
    )
    (net (code "86") (name "unconnected-(U11-RB-Pad10)") (class "Default")
      (node (ref "U11") (pin "10") (pinfunction "RB_10") (pintype "passive"))
    )
    (net (code "87") (name "unconnected-(U11-RC-Pad19)") (class "Default")
      (node (ref "U11") (pin "19") (pinfunction "RC_19") (pintype "passive"))
    )
    (net (code "88") (name "unconnected-(U11-RD-Pad20)") (class "Default")
      (node (ref "U11") (pin "20") (pinfunction "RD_20") (pintype "passive"))
    )
    (net (code "89") (name "unconnected-(U12-MCLKOUT-Pad3)") (class "Default")
      (node (ref "U12") (pin "3") (pinfunction "MCLKOUT_3") (pintype "passive"))
    )
    (net (code "90") (name "unconnected-(U12-P0-Pad7)") (class "Default")
      (node (ref "U12") (pin "7") (pinfunction "P0_7") (pintype "passive"))
    )
    (net (code "91") (name "unconnected-(U12-RA-Pad9)") (class "Default")
      (node (ref "U12") (pin "9") (pinfunction "RA_9") (pintype "passive"))
    )
    (net (code "92") (name "unconnected-(U12-RB-Pad10)") (class "Default")
      (node (ref "U12") (pin "10") (pinfunction "RB_10") (pintype "passive"))
    )
    (net (code "93") (name "unconnected-(U12-RC-Pad19)") (class "Default")
      (node (ref "U12") (pin "19") (pinfunction "RC_19") (pintype "passive"))
    )
    (net (code "94") (name "unconnected-(U12-RD-Pad20)") (class "Default")
      (node (ref "U12") (pin "20") (pinfunction "RD_20") (pintype "passive"))
    )
  )
)
